# new_sawtag_2012.net
KiCad netlist of a schematic drawn in EAGLE
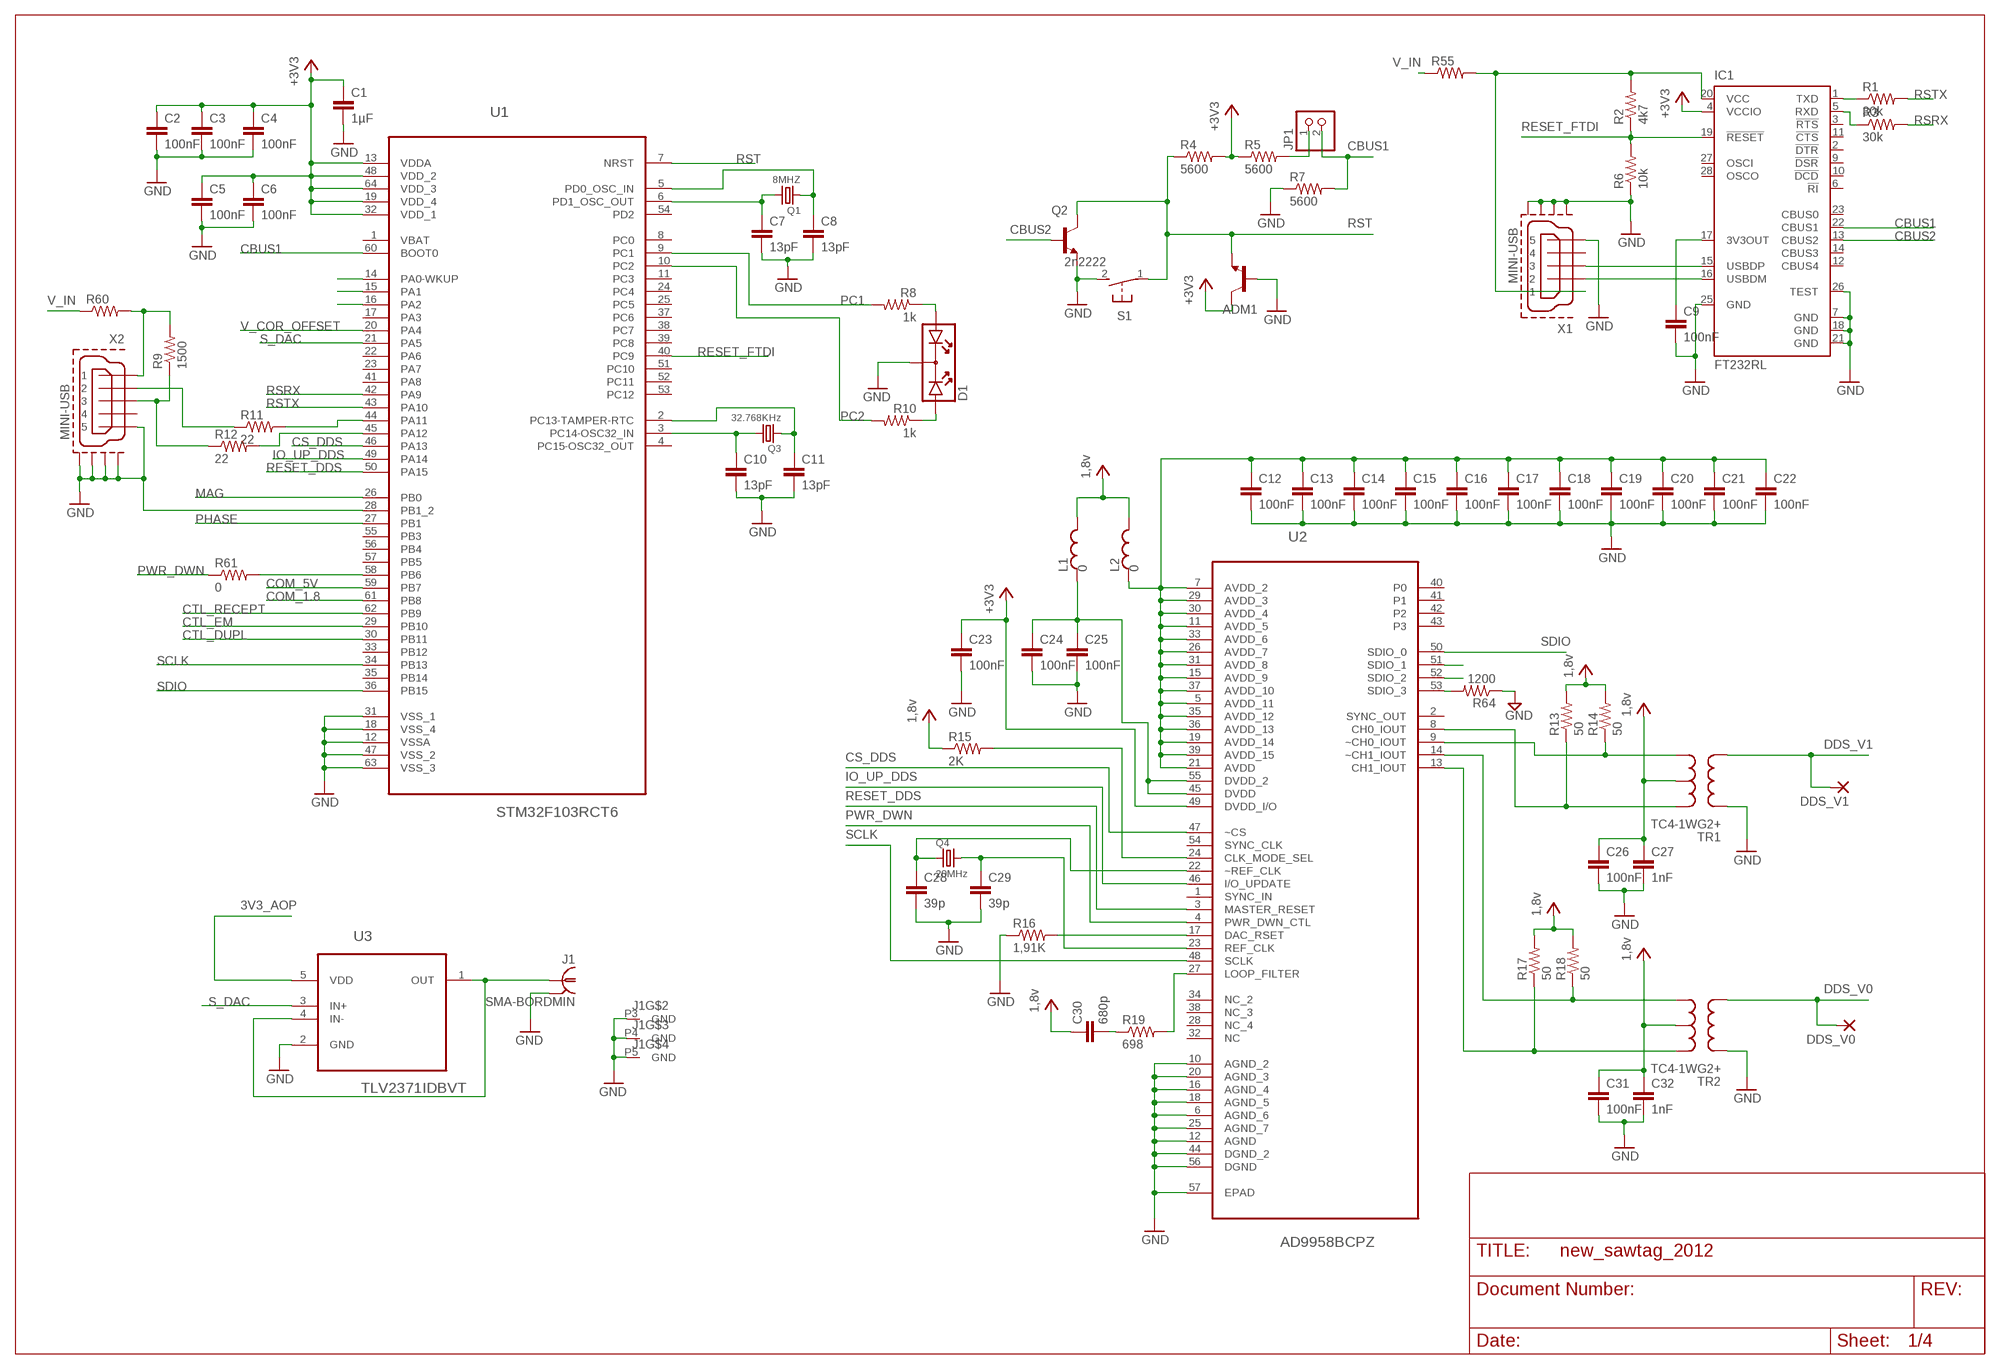
[diagram p0: schematic, sheet 1]
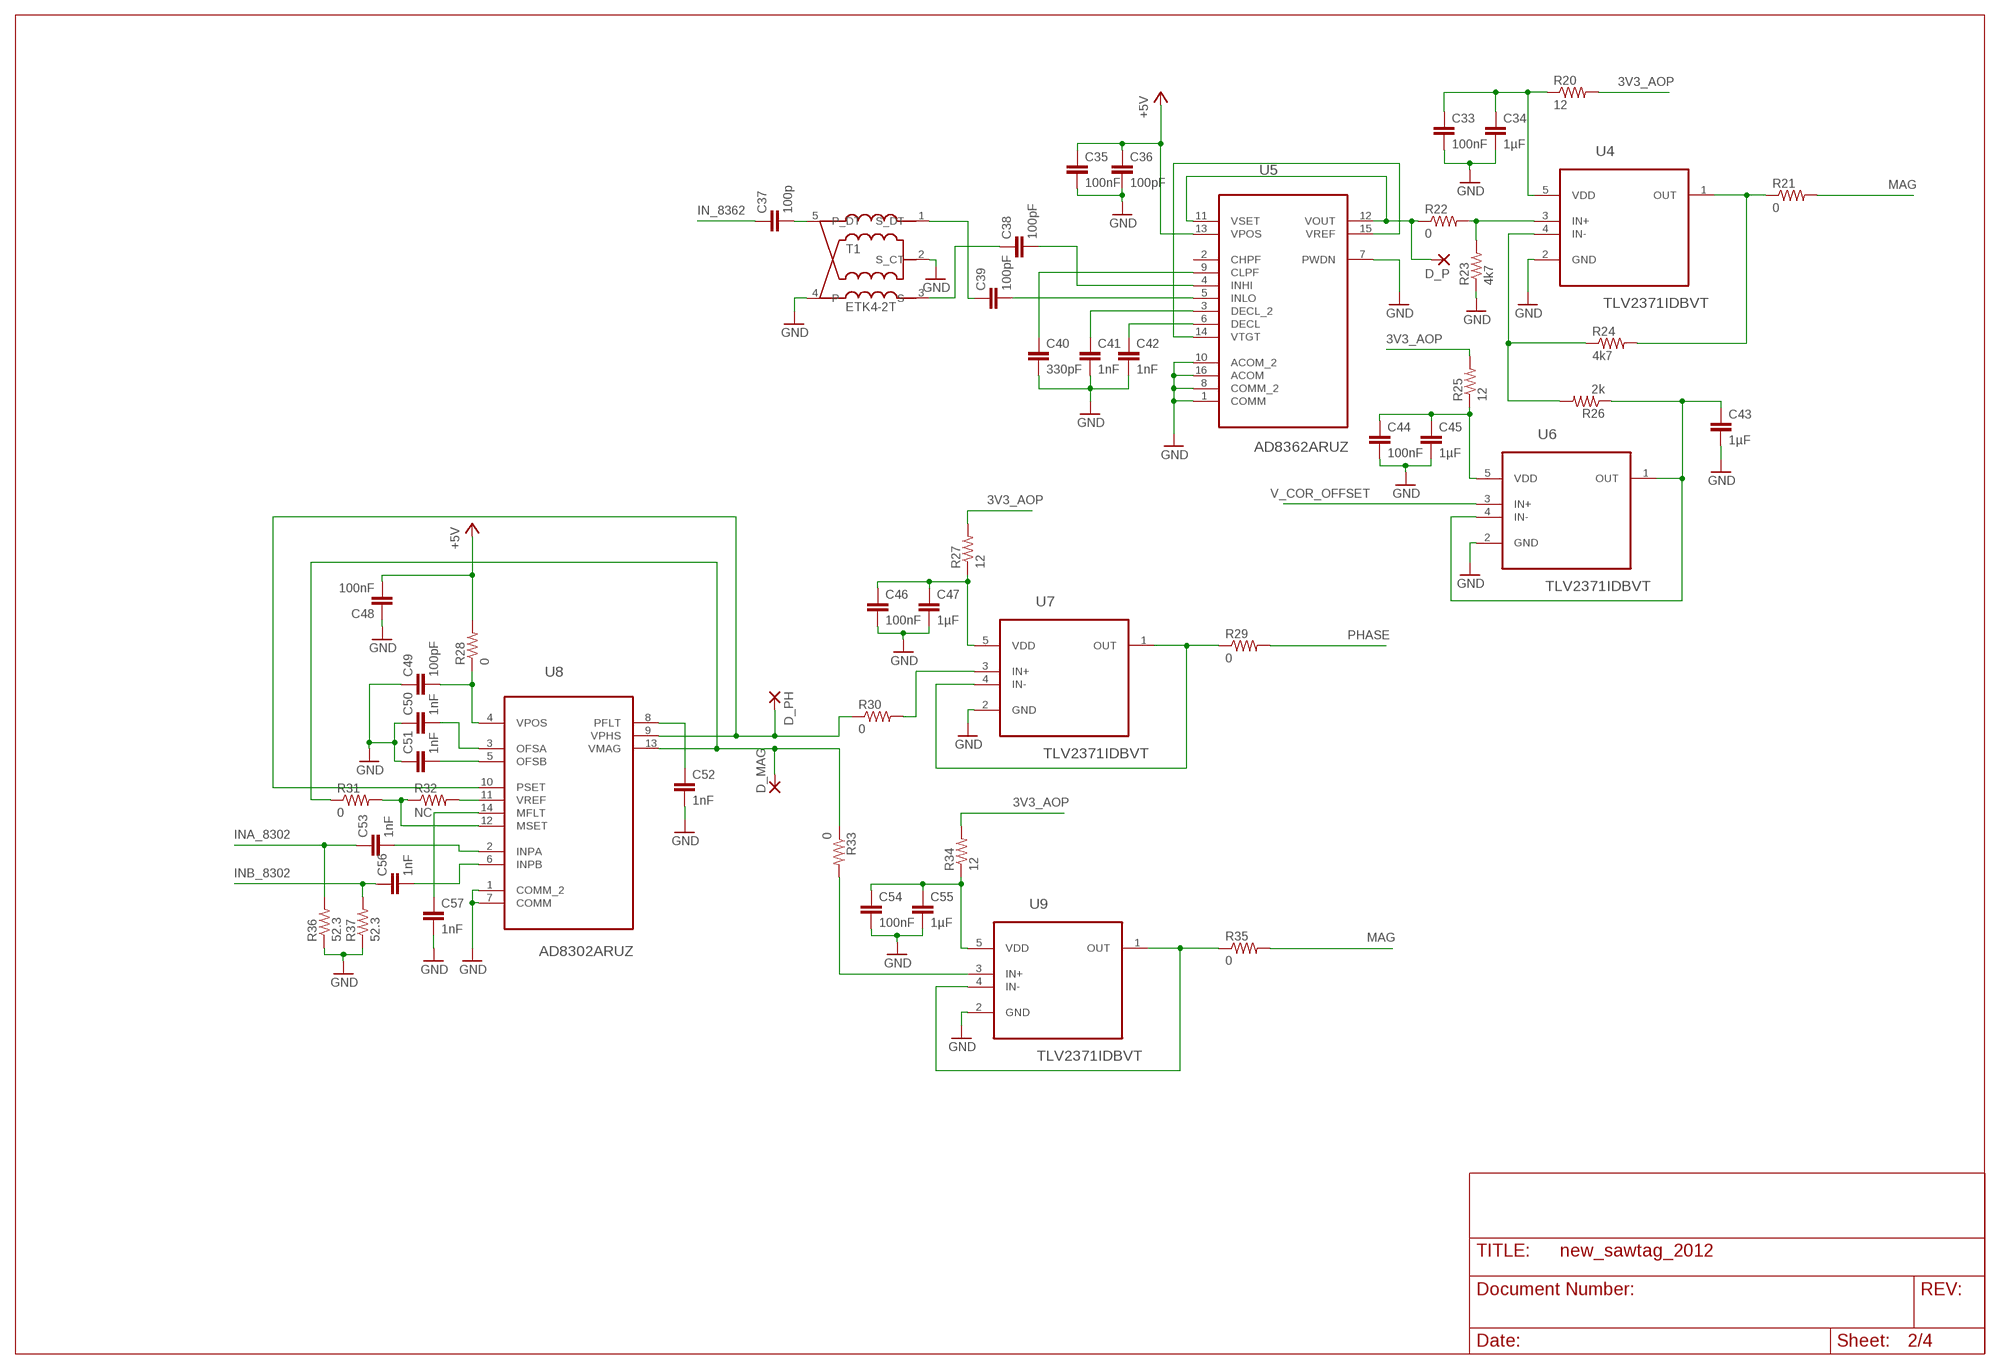
[diagram p1: schematic, sheet 2]
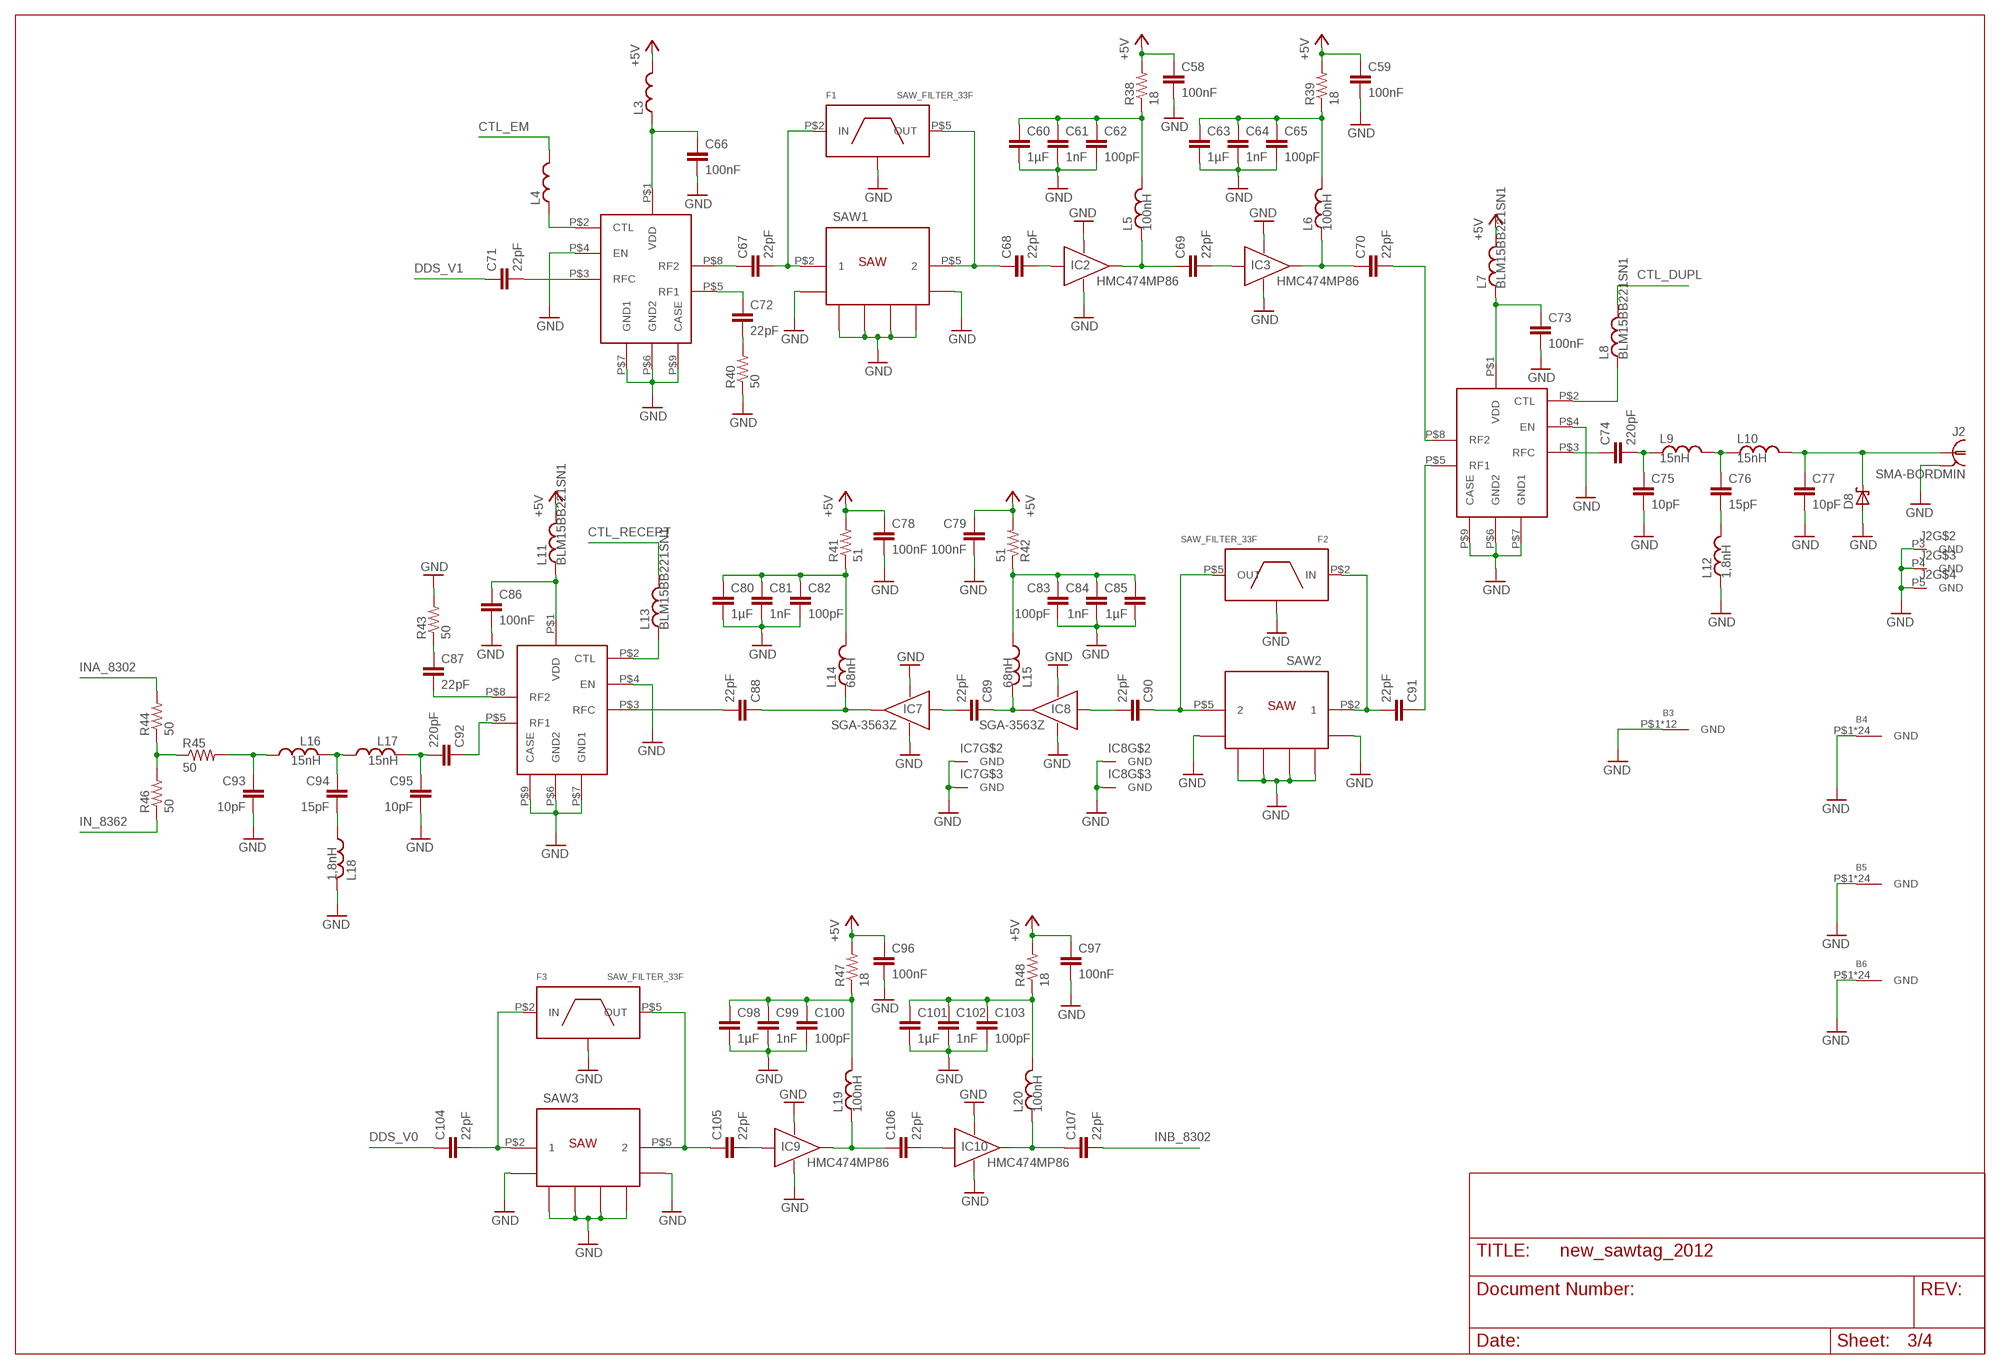
[diagram p2: schematic, sheet 3]
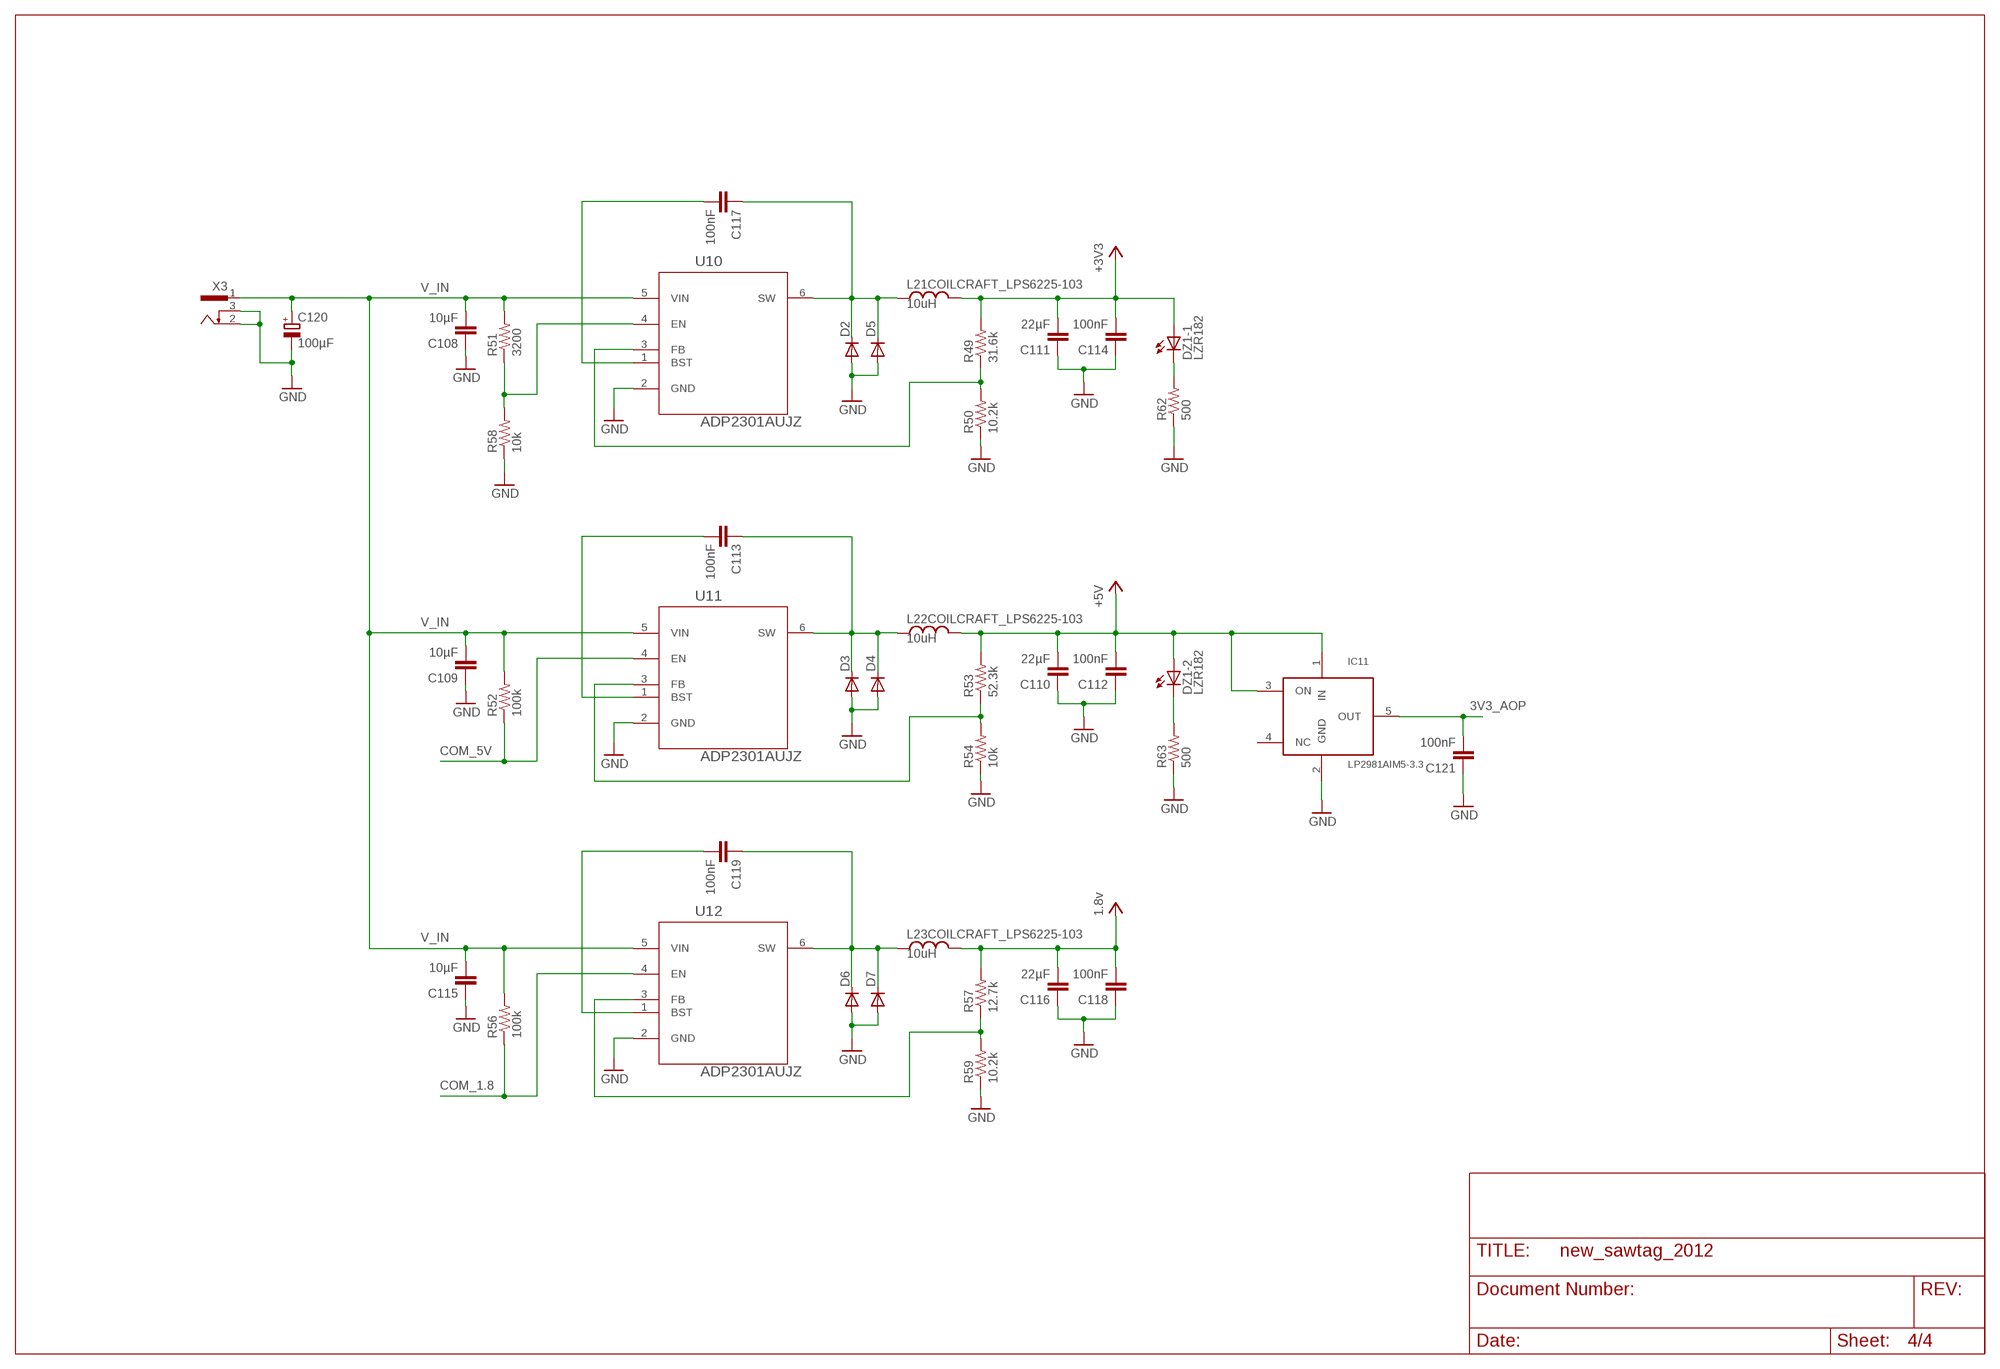
[diagram p3: schematic, sheet 4]

(export (version "E")
  (design (tool "Eeschema 10.0.6"))
  (components
    (comp (ref "ADM1")
      (value "TRANSISTOR_NPNSOT23")
      (footprint "eagle-import:SOT23")
      (libsource (lib "eagle-import") (part "TRANSISTOR_NPNSOT23"))
    )
    (comp (ref "C1")
      (value "1µF")
      (footprint "eagle-import:C0805")
      (libsource (lib "eagle-import") (part "C-EUC0805"))
    )
    (comp (ref "C2")
      (value "100nF")
      (footprint "eagle-import:C0603")
      (libsource (lib "eagle-import") (part "C-EUC0603"))
    )
    (comp (ref "C3")
      (value "100nF")
      (footprint "eagle-import:C0603")
      (libsource (lib "eagle-import") (part "C-EUC0603"))
    )
    (comp (ref "C4")
      (value "100nF")
      (footprint "eagle-import:C0603")
      (libsource (lib "eagle-import") (part "C-EUC0603"))
    )
    (comp (ref "C5")
      (value "100nF")
      (footprint "eagle-import:C0603")
      (libsource (lib "eagle-import") (part "C-EUC0603"))
    )
    (comp (ref "C6")
      (value "100nF")
      (footprint "eagle-import:C0603")
      (libsource (lib "eagle-import") (part "C-EUC0603"))
    )
    (comp (ref "C7")
      (value "13pF")
      (footprint "eagle-import:C0603")
      (libsource (lib "eagle-import") (part "C-EUC0603"))
    )
    (comp (ref "C8")
      (value "13pF")
      (footprint "eagle-import:C0603")
      (libsource (lib "eagle-import") (part "C-EUC0603"))
    )
    (comp (ref "C9")
      (value "100nF")
      (footprint "eagle-import:C0603")
      (libsource (lib "eagle-import") (part "C-EUC0603"))
    )
    (comp (ref "C10")
      (value "13pF")
      (footprint "eagle-import:C0603")
      (libsource (lib "eagle-import") (part "C-EUC0603"))
    )
    (comp (ref "C11")
      (value "13pF")
      (footprint "eagle-import:C0603")
      (libsource (lib "eagle-import") (part "C-EUC0603"))
    )
    (comp (ref "C12")
      (value "100nF")
      (footprint "eagle-import:C0402")
      (libsource (lib "eagle-import") (part "C-EUC0402"))
    )
    (comp (ref "C13")
      (value "100nF")
      (footprint "eagle-import:C0402")
      (libsource (lib "eagle-import") (part "C-EUC0402"))
    )
    (comp (ref "C14")
      (value "100nF")
      (footprint "eagle-import:C0402")
      (libsource (lib "eagle-import") (part "C-EUC0402"))
    )
    (comp (ref "C15")
      (value "100nF")
      (footprint "eagle-import:C0402")
      (libsource (lib "eagle-import") (part "C-EUC0402"))
    )
    (comp (ref "C16")
      (value "100nF")
      (footprint "eagle-import:C0402")
      (libsource (lib "eagle-import") (part "C-EUC0402"))
    )
    (comp (ref "C17")
      (value "100nF")
      (footprint "eagle-import:C0402")
      (libsource (lib "eagle-import") (part "C-EUC0402"))
    )
    (comp (ref "C18")
      (value "100nF")
      (footprint "eagle-import:C0402")
      (libsource (lib "eagle-import") (part "C-EUC0402"))
    )
    (comp (ref "C19")
      (value "100nF")
      (footprint "eagle-import:C0402")
      (libsource (lib "eagle-import") (part "C-EUC0402"))
    )
    (comp (ref "C20")
      (value "100nF")
      (footprint "eagle-import:C0402")
      (libsource (lib "eagle-import") (part "C-EUC0402"))
    )
    (comp (ref "C21")
      (value "100nF")
      (footprint "eagle-import:C0402")
      (libsource (lib "eagle-import") (part "C-EUC0402"))
    )
    (comp (ref "C22")
      (value "100nF")
      (footprint "eagle-import:C0402")
      (libsource (lib "eagle-import") (part "C-EUC0402"))
    )
    (comp (ref "C23")
      (value "100nF")
      (footprint "eagle-import:C0603")
      (libsource (lib "eagle-import") (part "C-EUC0603"))
    )
    (comp (ref "C24")
      (value "100nF")
      (footprint "eagle-import:C0603")
      (libsource (lib "eagle-import") (part "C-EUC0603"))
    )
    (comp (ref "C25")
      (value "100nF")
      (footprint "eagle-import:C0603")
      (libsource (lib "eagle-import") (part "C-EUC0603"))
    )
    (comp (ref "C26")
      (value "100nF")
      (footprint "eagle-import:C0603")
      (libsource (lib "eagle-import") (part "C-EUC0603"))
    )
    (comp (ref "C27")
      (value "1nF")
      (footprint "eagle-import:C0402")
      (libsource (lib "eagle-import") (part "C-EUC0402"))
    )
    (comp (ref "C28")
      (value "39p")
      (footprint "eagle-import:C0402")
      (libsource (lib "eagle-import") (part "C-EUC0402"))
    )
    (comp (ref "C29")
      (value "39p")
      (footprint "eagle-import:C0402")
      (libsource (lib "eagle-import") (part "C-EUC0402"))
    )
    (comp (ref "C30")
      (value "680p")
      (footprint "eagle-import:C0402")
      (libsource (lib "eagle-import") (part "C-EUC0402"))
    )
    (comp (ref "C31")
      (value "100nF")
      (footprint "eagle-import:C0603")
      (libsource (lib "eagle-import") (part "C-EUC0603"))
    )
    (comp (ref "C32")
      (value "1nF")
      (footprint "eagle-import:C0402")
      (libsource (lib "eagle-import") (part "C-EUC0402"))
    )
    (comp (ref "D1")
      (value "DUOLED")
      (footprint "eagle-import:DUOLED")
      (libsource (lib "eagle-import") (part "DUOLED"))
    )
    (comp (ref "DDS_V0")
      (value "1,6/0,8")
      (footprint "eagle-import:1,6_0,8")
      (libsource (lib "eagle-import") (part "1,6/0,8"))
    )
    (comp (ref "DDS_V1")
      (value "1,6/0,8")
      (footprint "eagle-import:1,6_0,8")
      (libsource (lib "eagle-import") (part "1,6/0,8"))
    )
    (comp (ref "IC1")
      (value "FT232RL")
      (footprint "eagle-import:SSOP28")
      (libsource (lib "eagle-import") (part "FT232RL"))
    )
    (comp (ref "J1")
      (value "SMA-BORDMIN")
      (footprint "eagle-import:SMA_BORDMIN")
      (libsource (lib "eagle-import") (part "SMA-BORDMIN"))
    )
    (comp (ref "JP1")
      (value "PINHD-1X2")
      (footprint "eagle-import:1X02")
      (libsource (lib "eagle-import") (part "PINHD-1X2"))
    )
    (comp (ref "L1")
      (value "0")
      (footprint "eagle-import:0603")
      (libsource (lib "eagle-import") (part "L_0603"))
    )
    (comp (ref "L2")
      (value "0")
      (footprint "eagle-import:0603")
      (libsource (lib "eagle-import") (part "L_0603"))
    )
    (comp (ref "Q1")
      (value "8MHZ")
      (footprint "eagle-import:SMD_5_3")
      (libsource (lib "eagle-import") (part "Q_20MHZ_SMD"))
    )
    (comp (ref "Q2")
      (value "2n2222")
      (footprint "eagle-import:SOT23")
      (libsource (lib "eagle-import") (part "TRANSISTOR_NPNSOT23"))
    )
    (comp (ref "Q3")
      (value "32.768KHz")
      (footprint "eagle-import:SMD_32K")
      (libsource (lib "eagle-import") (part "Q_32K_SMD"))
    )
    (comp (ref "Q4")
      (value "20MHz")
      (footprint "eagle-import:SMD_5_3")
      (libsource (lib "eagle-import") (part "Q_20MHZ_SMD"))
    )
    (comp (ref "R1")
      (value "30k")
      (footprint "eagle-import:R0402")
      (libsource (lib "eagle-import") (part "R-US_R0402"))
    )
    (comp (ref "R2")
      (value "4k7")
      (footprint "eagle-import:R0402")
      (libsource (lib "eagle-import") (part "R-US_R0402"))
    )
    (comp (ref "R3")
      (value "30k")
      (footprint "eagle-import:R0402")
      (libsource (lib "eagle-import") (part "R-US_R0402"))
    )
    (comp (ref "R4")
      (value "5600")
      (footprint "eagle-import:R0603")
      (libsource (lib "eagle-import") (part "R-US_R0603"))
    )
    (comp (ref "R5")
      (value "5600")
      (footprint "eagle-import:R0603")
      (libsource (lib "eagle-import") (part "R-US_R0603"))
    )
    (comp (ref "R6")
      (value "10k")
      (footprint "eagle-import:R0402")
      (libsource (lib "eagle-import") (part "R-US_R0402"))
    )
    (comp (ref "R7")
      (value "5600")
      (footprint "eagle-import:R0603")
      (libsource (lib "eagle-import") (part "R-US_R0603"))
    )
    (comp (ref "R8")
      (value "1k")
      (footprint "eagle-import:R0603")
      (libsource (lib "eagle-import") (part "R-US_R0603"))
    )
    (comp (ref "R9")
      (value "1500")
      (footprint "eagle-import:R1206")
      (libsource (lib "eagle-import") (part "R-US_R1206"))
    )
    (comp (ref "R10")
      (value "1k")
      (footprint "eagle-import:R0603")
      (libsource (lib "eagle-import") (part "R-US_R0603"))
    )
    (comp (ref "R11")
      (value "22")
      (footprint "eagle-import:R0603")
      (libsource (lib "eagle-import") (part "R-US_R0603"))
    )
    (comp (ref "R12")
      (value "22")
      (footprint "eagle-import:R0603")
      (libsource (lib "eagle-import") (part "R-US_R0603"))
    )
    (comp (ref "R13")
      (value "50")
      (footprint "eagle-import:R0402")
      (libsource (lib "eagle-import") (part "R-US_R0402"))
    )
    (comp (ref "R14")
      (value "50")
      (footprint "eagle-import:R0402")
      (libsource (lib "eagle-import") (part "R-US_R0402"))
    )
    (comp (ref "R15")
      (value "2K")
      (footprint "eagle-import:R0402")
      (libsource (lib "eagle-import") (part "R-US_R0402"))
    )
    (comp (ref "R16")
      (value "1,91K")
      (footprint "eagle-import:R0402")
      (libsource (lib "eagle-import") (part "R-US_R0402"))
    )
    (comp (ref "R17")
      (value "50")
      (footprint "eagle-import:R0402")
      (libsource (lib "eagle-import") (part "R-US_R0402"))
    )
    (comp (ref "R18")
      (value "50")
      (footprint "eagle-import:R0402")
      (libsource (lib "eagle-import") (part "R-US_R0402"))
    )
    (comp (ref "R19")
      (value "698")
      (footprint "eagle-import:R0402")
      (libsource (lib "eagle-import") (part "R-US_R0402"))
    )
    (comp (ref "R55")
      (value "R-US_R2512")
      (footprint "eagle-import:R2512")
      (libsource (lib "eagle-import") (part "R-US_R2512"))
    )
    (comp (ref "R60")
      (value "R-US_R2512")
      (footprint "eagle-import:R2512")
      (libsource (lib "eagle-import") (part "R-US_R2512"))
    )
    (comp (ref "R61")
      (value "0")
      (footprint "eagle-import:R0603")
      (libsource (lib "eagle-import") (part "R-US_R0603"))
    )
    (comp (ref "R64")
      (value "1200")
      (footprint "eagle-import:R0402")
      (libsource (lib "eagle-import") (part "R-US_R0402"))
    )
    (comp (ref "S1")
      (value "31-XX")
      (footprint "eagle-import:B3F-31XX")
      (fields (field (name "MPN") "B3F-3100"))
      (libsource (lib "eagle-import") (part "31-XX"))
    )
    (comp (ref "TR1")
      (value "TC4-1WG2+")
      (footprint "eagle-import:AT224-3")
      (libsource (lib "eagle-import") (part "TC4-1WG2+"))
    )
    (comp (ref "TR2")
      (value "TC4-1WG2+")
      (footprint "eagle-import:AT224-3")
      (libsource (lib "eagle-import") (part "TC4-1WG2+"))
    )
    (comp (ref "U1")
      (value "STM32F103RCT6")
      (footprint "eagle-import:QFP50P1200X1200X160-64N")
      (libsource (lib "eagle-import") (part "STM32F103RCT6"))
    )
    (comp (ref "U2")
      (value "AD9958BCPZ")
      (footprint "eagle-import:QFN50P800X800X100-57N")
      (libsource (lib "eagle-import") (part "AD9958BCPZ"))
    )
    (comp (ref "U3")
      (value "TLV2371IDBVT")
      (footprint "eagle-import:SOT95P280X145-5N")
      (libsource (lib "eagle-import") (part "TLV2371IDBVT"))
    )
    (comp (ref "X1")
      (value "MINI-USB")
      (footprint "eagle-import:UX60-MB-5ST")
      (libsource (lib "eagle-import") (part "MINI-USB-SHIELD-UX60-MB-5ST"))
    )
    (comp (ref "X2")
      (value "MINI-USB")
      (footprint "eagle-import:UX60-MB-5ST")
      (libsource (lib "eagle-import") (part "MINI-USB-SHIELD-UX60-MB-5ST"))
    )
    (comp (ref "C108")
      (value "10µF")
      (footprint "eagle-import:C0805")
      (libsource (lib "eagle-import") (part "C-EUC0805"))
    )
    (comp (ref "C109")
      (value "10µF")
      (footprint "eagle-import:C0805")
      (libsource (lib "eagle-import") (part "C-EUC0805"))
    )
    (comp (ref "C110")
      (value "22µF")
      (footprint "eagle-import:C0805")
      (libsource (lib "eagle-import") (part "C-EUC0805"))
    )
    (comp (ref "C111")
      (value "22µF")
      (footprint "eagle-import:C0805")
      (libsource (lib "eagle-import") (part "C-EUC0805"))
    )
    (comp (ref "C112")
      (value "100nF")
      (footprint "eagle-import:C0805")
      (libsource (lib "eagle-import") (part "C-EUC0805"))
    )
    (comp (ref "C113")
      (value "100nF")
      (footprint "eagle-import:C0805")
      (libsource (lib "eagle-import") (part "C-EUC0805"))
    )
    (comp (ref "C114")
      (value "100nF")
      (footprint "eagle-import:C0805")
      (libsource (lib "eagle-import") (part "C-EUC0805"))
    )
    (comp (ref "C115")
      (value "10µF")
      (footprint "eagle-import:C0805")
      (libsource (lib "eagle-import") (part "C-EUC0805"))
    )
    (comp (ref "C116")
      (value "22µF")
      (footprint "eagle-import:C0805")
      (libsource (lib "eagle-import") (part "C-EUC0805"))
    )
    (comp (ref "C117")
      (value "100nF")
      (footprint "eagle-import:C0805")
      (libsource (lib "eagle-import") (part "C-EUC0805"))
    )
    (comp (ref "C118")
      (value "100nF")
      (footprint "eagle-import:C0805")
      (libsource (lib "eagle-import") (part "C-EUC0805"))
    )
    (comp (ref "C119")
      (value "100nF")
      (footprint "eagle-import:C0603")
      (libsource (lib "eagle-import") (part "C-EUC0603"))
    )
    (comp (ref "C120")
      (value "100µF")
      (footprint "eagle-import:140CLH-1010")
      (libsource (lib "eagle-import") (part "CPOL-EU140CLH-1010"))
    )
    (comp (ref "C121")
      (value "100nF")
      (footprint "eagle-import:C0805")
      (libsource (lib "eagle-import") (part "C-EUC0805"))
    )
    (comp (ref "D2")
      (value "DIODE-SMB")
      (footprint "eagle-import:SMB")
      (libsource (lib "eagle-import") (part "DIODE-SMB"))
    )
    (comp (ref "D3")
      (value "DIODE-SMB")
      (footprint "eagle-import:SMB")
      (libsource (lib "eagle-import") (part "DIODE-SMB"))
    )
    (comp (ref "D4")
      (value "DIODE-SMC")
      (footprint "eagle-import:SMC")
      (libsource (lib "eagle-import") (part "DIODE-SMC"))
    )
    (comp (ref "D5")
      (value "DIODE-SMC")
      (footprint "eagle-import:SMC")
      (libsource (lib "eagle-import") (part "DIODE-SMC"))
    )
    (comp (ref "D6")
      (value "DIODE-SMB")
      (footprint "eagle-import:SMB")
      (libsource (lib "eagle-import") (part "DIODE-SMB"))
    )
    (comp (ref "D7")
      (value "DIODE-SMC")
      (footprint "eagle-import:SMC")
      (libsource (lib "eagle-import") (part "DIODE-SMC"))
    )
    (comp (ref "DZ1")
      (value "LZR182")
      (footprint "eagle-import:LZR182")
      (libsource (lib "eagle-import") (part "LZR182"))
    )
    (comp (ref "IC11")
      (value "LP2981AIM5-3.3")
      (footprint "eagle-import:SOT23-M5")
      (libsource (lib "eagle-import") (part "LP2981AIM5-3.3"))
    )
    (comp (ref "L21COILCRAFT_LPS6225-103")
      (value "10uH")
      (footprint "eagle-import:L_DCDC_6_6")
      (libsource (lib "eagle-import") (part "LPS6225"))
    )
    (comp (ref "L22COILCRAFT_LPS6225-103")
      (value "10uH")
      (footprint "eagle-import:L_DCDC_6_6")
      (libsource (lib "eagle-import") (part "LPS6225"))
    )
    (comp (ref "L23COILCRAFT_LPS6225-103")
      (value "10uH")
      (footprint "eagle-import:L_DCDC_6_6")
      (libsource (lib "eagle-import") (part "LPS6225"))
    )
    (comp (ref "R49")
      (value "31.6k")
      (footprint "eagle-import:R0603")
      (libsource (lib "eagle-import") (part "R-US_R0603"))
    )
    (comp (ref "R50")
      (value "10.2k")
      (footprint "eagle-import:R0603")
      (libsource (lib "eagle-import") (part "R-US_R0603"))
    )
    (comp (ref "R51")
      (value "3200")
      (footprint "eagle-import:R0603")
      (libsource (lib "eagle-import") (part "R-US_R0603"))
    )
    (comp (ref "R52")
      (value "100k")
      (footprint "eagle-import:R0603")
      (libsource (lib "eagle-import") (part "R-US_R0603"))
    )
    (comp (ref "R53")
      (value "52.3k")
      (footprint "eagle-import:R0603")
      (libsource (lib "eagle-import") (part "R-US_R0603"))
    )
    (comp (ref "R54")
      (value "10k")
      (footprint "eagle-import:R0603")
      (libsource (lib "eagle-import") (part "R-US_R0603"))
    )
    (comp (ref "R56")
      (value "100k")
      (footprint "eagle-import:R0603")
      (libsource (lib "eagle-import") (part "R-US_R0603"))
    )
    (comp (ref "R57")
      (value "12.7k")
      (footprint "eagle-import:R0603")
      (libsource (lib "eagle-import") (part "R-US_R0603"))
    )
    (comp (ref "R58")
      (value "10k")
      (footprint "eagle-import:R0603")
      (libsource (lib "eagle-import") (part "R-US_R0603"))
    )
    (comp (ref "R59")
      (value "10.2k")
      (footprint "eagle-import:R0603")
      (libsource (lib "eagle-import") (part "R-US_R0603"))
    )
    (comp (ref "R62")
      (value "500")
      (footprint "eagle-import:R0402")
      (libsource (lib "eagle-import") (part "R-US_R0402"))
    )
    (comp (ref "R63")
      (value "500")
      (footprint "eagle-import:R0402")
      (libsource (lib "eagle-import") (part "R-US_R0402"))
    )
    (comp (ref "U10")
      (value "ADP2301AUJZ")
      (footprint "eagle-import:SOT95P280X90-6N")
      (libsource (lib "eagle-import") (part "ADP2301AUJZ"))
    )
    (comp (ref "U11")
      (value "ADP2301AUJZ")
      (footprint "eagle-import:SOT95P280X90-6N")
      (libsource (lib "eagle-import") (part "ADP2301AUJZ"))
    )
    (comp (ref "U12")
      (value "ADP2301AUJZ")
      (footprint "eagle-import:SOT95P280X90-6N")
      (libsource (lib "eagle-import") (part "ADP2301AUJZ"))
    )
    (comp (ref "X3")
      (value "733980-62")
      (footprint "eagle-import:733980-62")
      (libsource (lib "eagle-import") (part "73398?0-62"))
    )
    (comp (ref "C33")
      (value "100nF")
      (footprint "eagle-import:C0402")
      (libsource (lib "eagle-import") (part "C-EUC0402"))
    )
    (comp (ref "C34")
      (value "1µF")
      (footprint "eagle-import:C0603")
      (libsource (lib "eagle-import") (part "C-EUC0603"))
    )
    (comp (ref "C35")
      (value "100nF")
      (footprint "eagle-import:C0603")
      (libsource (lib "eagle-import") (part "C-EUC0603"))
    )
    (comp (ref "C36")
      (value "100pF")
      (footprint "eagle-import:C0603")
      (libsource (lib "eagle-import") (part "C-EUC0603"))
    )
    (comp (ref "C37")
      (value "100p")
      (footprint "eagle-import:C0402")
      (libsource (lib "eagle-import") (part "C-EUC0402"))
    )
    (comp (ref "C38")
      (value "100pF")
      (footprint "eagle-import:C0402")
      (libsource (lib "eagle-import") (part "C-EUC0402"))
    )
    (comp (ref "C39")
      (value "100pF")
      (footprint "eagle-import:C0402")
      (libsource (lib "eagle-import") (part "C-EUC0402"))
    )
    (comp (ref "C40")
      (value "330pF")
      (footprint "eagle-import:C0603")
      (libsource (lib "eagle-import") (part "C-EUC0603"))
    )
    (comp (ref "C41")
      (value "1nF")
      (footprint "eagle-import:C0603")
      (libsource (lib "eagle-import") (part "C-EUC0603"))
    )
    (comp (ref "C42")
      (value "1nF")
      (footprint "eagle-import:C0603")
      (libsource (lib "eagle-import") (part "C-EUC0603"))
    )
    (comp (ref "C43")
      (value "1µF")
      (footprint "eagle-import:C0603")
      (libsource (lib "eagle-import") (part "C-EUC0603"))
    )
    (comp (ref "C44")
      (value "100nF")
      (footprint "eagle-import:C0402")
      (libsource (lib "eagle-import") (part "C-EUC0402"))
    )
    (comp (ref "C45")
      (value "1µF")
      (footprint "eagle-import:C0603")
      (libsource (lib "eagle-import") (part "C-EUC0603"))
    )
    (comp (ref "C46")
      (value "100nF")
      (footprint "eagle-import:C0402")
      (libsource (lib "eagle-import") (part "C-EUC0402"))
    )
    (comp (ref "C47")
      (value "1µF")
      (footprint "eagle-import:C0603")
      (libsource (lib "eagle-import") (part "C-EUC0603"))
    )
    (comp (ref "C48")
      (value "100nF")
      (footprint "eagle-import:C0603")
      (libsource (lib "eagle-import") (part "C-EUC0603"))
    )
    (comp (ref "C49")
      (value "100pF")
      (footprint "eagle-import:C0402")
      (libsource (lib "eagle-import") (part "C-EUC0402"))
    )
    (comp (ref "C50")
      (value "1nF")
      (footprint "eagle-import:C0402")
      (libsource (lib "eagle-import") (part "C-EUC0402"))
    )
    (comp (ref "C51")
      (value "1nF")
      (footprint "eagle-import:C0402")
      (libsource (lib "eagle-import") (part "C-EUC0402"))
    )
    (comp (ref "C52")
      (value "1nF")
      (footprint "eagle-import:C0402")
      (libsource (lib "eagle-import") (part "C-EUC0402"))
    )
    (comp (ref "C53")
      (value "1nF")
      (footprint "eagle-import:C0402")
      (libsource (lib "eagle-import") (part "C-EUC0402"))
    )
    (comp (ref "C54")
      (value "100nF")
      (footprint "eagle-import:C0402")
      (libsource (lib "eagle-import") (part "C-EUC0402"))
    )
    (comp (ref "C55")
      (value "1µF")
      (footprint "eagle-import:C0603")
      (libsource (lib "eagle-import") (part "C-EUC0603"))
    )
    (comp (ref "C56")
      (value "1nF")
      (footprint "eagle-import:C0402")
      (libsource (lib "eagle-import") (part "C-EUC0402"))
    )
    (comp (ref "C57")
      (value "1nF")
      (footprint "eagle-import:C0402")
      (libsource (lib "eagle-import") (part "C-EUC0402"))
    )
    (comp (ref "D_MAG")
      (value "1,6/0,8")
      (footprint "eagle-import:1,6_0,8")
      (libsource (lib "eagle-import") (part "1,6/0,8"))
    )
    (comp (ref "D_P")
      (value "1,6/0,8")
      (footprint "eagle-import:1,6_0,8")
      (libsource (lib "eagle-import") (part "1,6/0,8"))
    )
    (comp (ref "D_PH")
      (value "1,6/0,8")
      (footprint "eagle-import:1,6_0,8")
      (libsource (lib "eagle-import") (part "1,6/0,8"))
    )
    (comp (ref "R20")
      (value "12")
      (footprint "eagle-import:R0603")
      (libsource (lib "eagle-import") (part "R-US_R0603"))
    )
    (comp (ref "R21")
      (value "0")
      (footprint "eagle-import:R0603")
      (libsource (lib "eagle-import") (part "R-US_R0603"))
    )
    (comp (ref "R22")
      (value "0")
      (footprint "eagle-import:R0603")
      (libsource (lib "eagle-import") (part "R-US_R0603"))
    )
    (comp (ref "R23")
      (value "4k7")
      (footprint "eagle-import:R0603")
      (libsource (lib "eagle-import") (part "R-US_R0603"))
    )
    (comp (ref "R24")
      (value "4k7")
      (footprint "eagle-import:R0603")
      (libsource (lib "eagle-import") (part "R-US_R0603"))
    )
    (comp (ref "R25")
      (value "12")
      (footprint "eagle-import:R0603")
      (libsource (lib "eagle-import") (part "R-US_R0603"))
    )
    (comp (ref "R26")
      (value "2k")
      (footprint "eagle-import:R0603")
      (libsource (lib "eagle-import") (part "R-US_R0603"))
    )
    (comp (ref "R27")
      (value "12")
      (footprint "eagle-import:R0603")
      (libsource (lib "eagle-import") (part "R-US_R0603"))
    )
    (comp (ref "R28")
      (value "0")
      (footprint "eagle-import:R0603")
      (libsource (lib "eagle-import") (part "R-US_R0603"))
    )
    (comp (ref "R29")
      (value "0")
      (footprint "eagle-import:R0603")
      (libsource (lib "eagle-import") (part "R-US_R0603"))
    )
    (comp (ref "R30")
      (value "0")
      (footprint "eagle-import:R0603")
      (libsource (lib "eagle-import") (part "R-US_R0603"))
    )
    (comp (ref "R31")
      (value "0")
      (footprint "eagle-import:R0603")
      (libsource (lib "eagle-import") (part "R-US_R0603"))
    )
    (comp (ref "R32")
      (value "NC")
      (footprint "eagle-import:R0603")
      (libsource (lib "eagle-import") (part "R-US_R0603"))
    )
    (comp (ref "R33")
      (value "0")
      (footprint "eagle-import:R0603")
      (libsource (lib "eagle-import") (part "R-US_R0603"))
    )
    (comp (ref "R34")
      (value "12")
      (footprint "eagle-import:R0603")
      (libsource (lib "eagle-import") (part "R-US_R0603"))
    )
    (comp (ref "R35")
      (value "0")
      (footprint "eagle-import:R0603")
      (libsource (lib "eagle-import") (part "R-US_R0603"))
    )
    (comp (ref "R36")
      (value "52.3")
      (footprint "eagle-import:R0603")
      (libsource (lib "eagle-import") (part "R-US_R0603"))
    )
    (comp (ref "R37")
      (value "52.3")
      (footprint "eagle-import:R0603")
      (libsource (lib "eagle-import") (part "R-US_R0603"))
    )
    (comp (ref "T1")
      (value "ETK4-2T")
      (footprint "eagle-import:SM-22")
      (libsource (lib "eagle-import") (part "ETK4-2T"))
    )
    (comp (ref "U4")
      (value "TLV2371IDBVT")
      (footprint "eagle-import:SOT95P280X145-5N")
      (libsource (lib "eagle-import") (part "TLV2371IDBVT"))
    )
    (comp (ref "U5")
      (value "AD8362ARUZ")
      (footprint "eagle-import:SOP65P640X120-16N")
      (libsource (lib "eagle-import") (part "AD8362ARUZ"))
    )
    (comp (ref "U6")
      (value "TLV2371IDBVT")
      (footprint "eagle-import:SOT95P280X145-5N")
      (fields
        (field (name "MPN") "TLV2371IDBVT")
        (field (name "OC_FARNELL") "8454990")
        (field (name "OC_NEWARK") "76C7970")
        (field (name "PACKAGE") "SOT-23-5")
        (field (name "SUPPLIER") "Texas Instruments")
      )
      (libsource (lib "eagle-import") (part "TLV2371IDBVT"))
    )
    (comp (ref "U7")
      (value "TLV2371IDBVT")
      (footprint "eagle-import:SOT95P280X145-5N")
      (fields
        (field (name "MPN") "TLV2371IDBVT")
        (field (name "OC_FARNELL") "8454990")
        (field (name "OC_NEWARK") "76C7970")
        (field (name "PACKAGE") "SOT-23-5")
        (field (name "SUPPLIER") "Texas Instruments")
      )
      (libsource (lib "eagle-import") (part "TLV2371IDBVT"))
    )
    (comp (ref "U8")
      (value "AD8302ARUZ")
      (footprint "eagle-import:SOP65P640X120-14N")
      (libsource (lib "eagle-import") (part "AD8302ARUZ"))
    )
    (comp (ref "U9")
      (value "TLV2371IDBVT")
      (footprint "eagle-import:SOT95P280X145-5N")
      (fields
        (field (name "MPN") "TLV2371IDBVT")
        (field (name "OC_FARNELL") "8454990")
        (field (name "OC_NEWARK") "76C7970")
        (field (name "PACKAGE") "SOT-23-5")
        (field (name "SUPPLIER") "Texas Instruments")
      )
      (libsource (lib "eagle-import") (part "TLV2371IDBVT"))
    )
    (comp (ref "B3")
      (value "BMIS-102")
      (footprint "eagle-import:BMIS-102")
      (libsource (lib "eagle-import") (part "BMIS-102"))
    )
    (comp (ref "B4")
      (value "BMIS-205")
      (footprint "eagle-import:BMIS-205")
      (libsource (lib "eagle-import") (part "BMIS-205"))
    )
    (comp (ref "B5")
      (value "BMIS-205")
      (footprint "eagle-import:BMIS-205")
      (libsource (lib "eagle-import") (part "BMIS-205"))
    )
    (comp (ref "B6")
      (value "BMIS-205")
      (footprint "eagle-import:BMIS-205")
      (libsource (lib "eagle-import") (part "BMIS-205"))
    )
    (comp (ref "C58")
      (value "100nF")
      (footprint "eagle-import:C0603")
      (libsource (lib "eagle-import") (part "C-EUC0603"))
    )
    (comp (ref "C59")
      (value "100nF")
      (footprint "eagle-import:C0603")
      (libsource (lib "eagle-import") (part "C-EUC0603"))
    )
    (comp (ref "C60")
      (value "1µF")
      (footprint "eagle-import:C0603")
      (libsource (lib "eagle-import") (part "C-EUC0603"))
    )
    (comp (ref "C61")
      (value "1nF")
      (footprint "eagle-import:C0402")
      (libsource (lib "eagle-import") (part "C-EUC0402"))
    )
    (comp (ref "C62")
      (value "100pF")
      (footprint "eagle-import:C0402")
      (libsource (lib "eagle-import") (part "C-EUC0402"))
    )
    (comp (ref "C63")
      (value "1µF")
      (footprint "eagle-import:C0603")
      (libsource (lib "eagle-import") (part "C-EUC0603"))
    )
    (comp (ref "C64")
      (value "1nF")
      (footprint "eagle-import:C0402")
      (libsource (lib "eagle-import") (part "C-EUC0402"))
    )
    (comp (ref "C65")
      (value "100pF")
      (footprint "eagle-import:C0402")
      (libsource (lib "eagle-import") (part "C-EUC0402"))
    )
    (comp (ref "C66")
      (value "100nF")
      (footprint "eagle-import:C0603")
      (libsource (lib "eagle-import") (part "C-EUC0603"))
    )
    (comp (ref "C67")
      (value "22pF")
      (footprint "eagle-import:C0402")
      (libsource (lib "eagle-import") (part "C-EUC0402"))
    )
    (comp (ref "C68")
      (value "22pF")
      (footprint "eagle-import:C0402")
      (libsource (lib "eagle-import") (part "C-EUC0402"))
    )
    (comp (ref "C69")
      (value "22pF")
      (footprint "eagle-import:C0402")
      (libsource (lib "eagle-import") (part "C-EUC0402"))
    )
    (comp (ref "C70")
      (value "22pF")
      (footprint "eagle-import:C0402")
      (libsource (lib "eagle-import") (part "C-EUC0402"))
    )
    (comp (ref "C71")
      (value "22pF")
      (footprint "eagle-import:C0402")
      (libsource (lib "eagle-import") (part "C-EUC0402"))
    )
    (comp (ref "C72")
      (value "22pF")
      (footprint "eagle-import:C0402")
      (libsource (lib "eagle-import") (part "C-EUC0402"))
    )
    (comp (ref "C73")
      (value "100nF")
      (footprint "eagle-import:C0402")
      (libsource (lib "eagle-import") (part "C-EUC0402"))
    )
    (comp (ref "C74")
      (value "220pF")
      (footprint "eagle-import:C0402")
      (libsource (lib "eagle-import") (part "C-EUC0402"))
    )
    (comp (ref "C75")
      (value "10pF")
      (footprint "eagle-import:C0402")
      (libsource (lib "eagle-import") (part "C-EUC0402"))
    )
    (comp (ref "C76")
      (value "15pF")
      (footprint "eagle-import:C0402")
      (libsource (lib "eagle-import") (part "C-EUC0402"))
    )
    (comp (ref "C77")
      (value "10pF")
      (footprint "eagle-import:C0402")
      (libsource (lib "eagle-import") (part "C-EUC0402"))
    )
    (comp (ref "C78")
      (value "100nF")
      (footprint "eagle-import:C0603")
      (libsource (lib "eagle-import") (part "C-EUC0603"))
    )
    (comp (ref "C79")
      (value "100nF")
      (footprint "eagle-import:C0603")
      (libsource (lib "eagle-import") (part "C-EUC0603"))
    )
    (comp (ref "C80")
      (value "1µF")
      (footprint "eagle-import:C0603")
      (libsource (lib "eagle-import") (part "C-EUC0603"))
    )
    (comp (ref "C81")
      (value "1nF")
      (footprint "eagle-import:C0402")
      (libsource (lib "eagle-import") (part "C-EUC0402"))
    )
    (comp (ref "C82")
      (value "100pF")
      (footprint "eagle-import:C0402")
      (libsource (lib "eagle-import") (part "C-EUC0402"))
    )
    (comp (ref "C83")
      (value "100pF")
      (footprint "eagle-import:C0402")
      (libsource (lib "eagle-import") (part "C-EUC0402"))
    )
    (comp (ref "C84")
      (value "1nF")
      (footprint "eagle-import:C0402")
      (libsource (lib "eagle-import") (part "C-EUC0402"))
    )
    (comp (ref "C85")
      (value "1µF")
      (footprint "eagle-import:C0603")
      (libsource (lib "eagle-import") (part "C-EUC0603"))
    )
    (comp (ref "C86")
      (value "100nF")
      (footprint "eagle-import:C0603")
      (libsource (lib "eagle-import") (part "C-EUC0603"))
    )
    (comp (ref "C87")
      (value "22pF")
      (footprint "eagle-import:C0402")
      (libsource (lib "eagle-import") (part "C-EUC0402"))
    )
    (comp (ref "C88")
      (value "22pF")
      (footprint "eagle-import:C0402")
      (libsource (lib "eagle-import") (part "C-EUC0402"))
    )
    (comp (ref "C89")
      (value "22pF")
      (footprint "eagle-import:C0402")
      (libsource (lib "eagle-import") (part "C-EUC0402"))
    )
    (comp (ref "C90")
      (value "22pF")
      (footprint "eagle-import:C0402")
      (libsource (lib "eagle-import") (part "C-EUC0402"))
    )
    (comp (ref "C91")
      (value "22pF")
      (footprint "eagle-import:C0402")
      (libsource (lib "eagle-import") (part "C-EUC0402"))
    )
    (comp (ref "C92")
      (value "220pF")
      (footprint "eagle-import:C0402")
      (libsource (lib "eagle-import") (part "C-EUC0402"))
    )
    (comp (ref "C93")
      (value "10pF")
      (footprint "eagle-import:C0402")
      (libsource (lib "eagle-import") (part "C-EUC0402"))
    )
    (comp (ref "C94")
      (value "15pF")
      (footprint "eagle-import:C0402")
      (libsource (lib "eagle-import") (part "C-EUC0402"))
    )
    (comp (ref "C95")
      (value "10pF")
      (footprint "eagle-import:C0402")
      (libsource (lib "eagle-import") (part "C-EUC0402"))
    )
    (comp (ref "C96")
      (value "100nF")
      (footprint "eagle-import:C0603")
      (libsource (lib "eagle-import") (part "C-EUC0603"))
    )
    (comp (ref "C97")
      (value "100nF")
      (footprint "eagle-import:C0603")
      (libsource (lib "eagle-import") (part "C-EUC0603"))
    )
    (comp (ref "C98")
      (value "1µF")
      (footprint "eagle-import:C0603")
      (libsource (lib "eagle-import") (part "C-EUC0603"))
    )
    (comp (ref "C99")
      (value "1nF")
      (footprint "eagle-import:C0402")
      (libsource (lib "eagle-import") (part "C-EUC0402"))
    )
    (comp (ref "C100")
      (value "100pF")
      (footprint "eagle-import:C0402")
      (libsource (lib "eagle-import") (part "C-EUC0402"))
    )
    (comp (ref "C101")
      (value "1µF")
      (footprint "eagle-import:C0603")
      (libsource (lib "eagle-import") (part "C-EUC0603"))
    )
    (comp (ref "C102")
      (value "1nF")
      (footprint "eagle-import:C0402")
      (libsource (lib "eagle-import") (part "C-EUC0402"))
    )
    (comp (ref "C103")
      (value "100pF")
      (footprint "eagle-import:C0402")
      (libsource (lib "eagle-import") (part "C-EUC0402"))
    )
    (comp (ref "C104")
      (value "22pF")
      (footprint "eagle-import:C0402")
      (libsource (lib "eagle-import") (part "C-EUC0402"))
    )
    (comp (ref "C105")
      (value "22pF")
      (footprint "eagle-import:C0402")
      (libsource (lib "eagle-import") (part "C-EUC0402"))
    )
    (comp (ref "C106")
      (value "22pF")
      (footprint "eagle-import:C0402")
      (libsource (lib "eagle-import") (part "C-EUC0402"))
    )
    (comp (ref "C107")
      (value "22pF")
      (footprint "eagle-import:C0402")
      (libsource (lib "eagle-import") (part "C-EUC0402"))
    )
    (comp (ref "D8")
      (value "SMF5.0AT1")
      (footprint "eagle-import:SOD123FL")
      (libsource (lib "eagle-import") (part "SMF5.0AT1"))
    )
    (comp (ref "F1")
      (value "SAW_FILTER_33F")
      (footprint "eagle-import:BOITIER_3-3")
      (libsource (lib "eagle-import") (part "SAW_FILTER_33F"))
    )
    (comp (ref "F2")
      (value "SAW_FILTER_33F")
      (footprint "eagle-import:BOITIER_3-3")
      (libsource (lib "eagle-import") (part "SAW_FILTER_33F"))
    )
    (comp (ref "F3")
      (value "SAW_FILTER_33F")
      (footprint "eagle-import:BOITIER_3-3")
      (libsource (lib "eagle-import") (part "SAW_FILTER_33F"))
    )
    (comp (ref "IC2")
      (value "HMC474MP86")
      (footprint "eagle-import:VV105")
      (libsource (lib "eagle-import") (part "HMC474MP86"))
    )
    (comp (ref "IC3")
      (value "HMC474MP86")
      (footprint "eagle-import:VV105")
      (libsource (lib "eagle-import") (part "HMC474MP86"))
    )
    (comp (ref "IC4")
      (value "HMC349MS8G")
      (footprint "eagle-import:SMT-MS8G")
      (libsource (lib "eagle-import") (part "HMC349MS8G"))
    )
    (comp (ref "IC5")
      (value "HMC349MS8G")
      (footprint "eagle-import:SMT-MS8G")
      (libsource (lib "eagle-import") (part "HMC349MS8G"))
    )
    (comp (ref "IC6")
      (value "HMC349MS8G")
      (footprint "eagle-import:SMT-MS8G")
      (libsource (lib "eagle-import") (part "HMC349MS8G"))
    )
    (comp (ref "IC7")
      (value "SGA-3563Z")
      (footprint "eagle-import:SOT363")
      (libsource (lib "eagle-import") (part "SGA-3563Z"))
    )
    (comp (ref "IC8")
      (value "SGA-3563Z")
      (footprint "eagle-import:SOT363")
      (libsource (lib "eagle-import") (part "SGA-3563Z"))
    )
    (comp (ref "IC9")
      (value "HMC474MP86")
      (footprint "eagle-import:VV105")
      (libsource (lib "eagle-import") (part "HMC474MP86"))
    )
    (comp (ref "IC10")
      (value "HMC474MP86")
      (footprint "eagle-import:VV105")
      (libsource (lib "eagle-import") (part "HMC474MP86"))
    )
    (comp (ref "J2")
      (value "SMA-BORDMIN")
      (footprint "eagle-import:SMA_BORDMIN")
      (libsource (lib "eagle-import") (part "SMA-BORDMIN"))
    )
    (comp (ref "L3")
      (value "L_0402")
      (footprint "eagle-import:0402")
      (libsource (lib "eagle-import") (part "L_0402"))
    )
    (comp (ref "L4")
      (value "L_0402")
      (footprint "eagle-import:0402")
      (libsource (lib "eagle-import") (part "L_0402"))
    )
    (comp (ref "L5")
      (value "100nH")
      (footprint "eagle-import:0603")
      (libsource (lib "eagle-import") (part "L_0603"))
    )
    (comp (ref "L6")
      (value "100nH")
      (footprint "eagle-import:0603")
      (libsource (lib "eagle-import") (part "L_0603"))
    )
    (comp (ref "L7")
      (value "BLM15BB221SN1")
      (footprint "eagle-import:0402")
      (libsource (lib "eagle-import") (part "L_0402"))
    )
    (comp (ref "L8")
      (value "BLM15BB221SN1")
      (footprint "eagle-import:0402")
      (libsource (lib "eagle-import") (part "L_0402"))
    )
    (comp (ref "L9")
      (value "15nH")
      (footprint "eagle-import:0603")
      (libsource (lib "eagle-import") (part "L_0603"))
    )
    (comp (ref "L10")
      (value "15nH")
      (footprint "eagle-import:0603")
      (libsource (lib "eagle-import") (part "L_0603"))
    )
    (comp (ref "L11")
      (value "BLM15BB221SN1")
      (footprint "eagle-import:0402")
      (libsource (lib "eagle-import") (part "L_0402"))
    )
    (comp (ref "L12")
      (value "1,8nH")
      (footprint "eagle-import:0603")
      (libsource (lib "eagle-import") (part "L_0603"))
    )
    (comp (ref "L13")
      (value "BLM15BB221SN1")
      (footprint "eagle-import:0402")
      (libsource (lib "eagle-import") (part "L_0402"))
    )
    (comp (ref "L14")
      (value "68nH")
      (footprint "eagle-import:0603")
      (libsource (lib "eagle-import") (part "L_0603"))
    )
    (comp (ref "L15")
      (value "68nH")
      (footprint "eagle-import:0603")
      (libsource (lib "eagle-import") (part "L_0603"))
    )
    (comp (ref "L16")
      (value "15nH")
      (footprint "eagle-import:0603")
      (libsource (lib "eagle-import") (part "L_0603"))
    )
    (comp (ref "L17")
      (value "15nH")
      (footprint "eagle-import:0603")
      (libsource (lib "eagle-import") (part "L_0603"))
    )
    (comp (ref "L18")
      (value "1,8nH")
      (footprint "eagle-import:0603")
      (libsource (lib "eagle-import") (part "L_0603"))
    )
    (comp (ref "L19")
      (value "100nH")
      (footprint "eagle-import:0603")
      (libsource (lib "eagle-import") (part "L_0603"))
    )
    (comp (ref "L20")
      (value "100nH")
      (footprint "eagle-import:0603")
      (libsource (lib "eagle-import") (part "L_0603"))
    )
    (comp (ref "R38")
      (value "18")
      (footprint "eagle-import:R0603")
      (libsource (lib "eagle-import") (part "R-US_R0603"))
    )
    (comp (ref "R39")
      (value "18")
      (footprint "eagle-import:R0603")
      (libsource (lib "eagle-import") (part "R-US_R0603"))
    )
    (comp (ref "R40")
      (value "50")
      (footprint "eagle-import:R0603")
      (libsource (lib "eagle-import") (part "R-US_R0603"))
    )
    (comp (ref "R41")
      (value "51")
      (footprint "eagle-import:R0603")
      (libsource (lib "eagle-import") (part "R-US_R0603"))
    )
    (comp (ref "R42")
      (value "51")
      (footprint "eagle-import:R0603")
      (libsource (lib "eagle-import") (part "R-US_R0603"))
    )
    (comp (ref "R43")
      (value "50")
      (footprint "eagle-import:R0402")
      (libsource (lib "eagle-import") (part "R-US_R0402"))
    )
    (comp (ref "R44")
      (value "50")
      (footprint "eagle-import:R0402")
      (libsource (lib "eagle-import") (part "R-US_R0402"))
    )
    (comp (ref "R45")
      (value "50")
      (footprint "eagle-import:R0402")
      (libsource (lib "eagle-import") (part "R-US_R0402"))
    )
    (comp (ref "R46")
      (value "50")
      (footprint "eagle-import:R0402")
      (libsource (lib "eagle-import") (part "R-US_R0402"))
    )
    (comp (ref "R47")
      (value "18")
      (footprint "eagle-import:R0603")
      (libsource (lib "eagle-import") (part "R-US_R0603"))
    )
    (comp (ref "R48")
      (value "18")
      (footprint "eagle-import:R0603")
      (libsource (lib "eagle-import") (part "R-US_R0603"))
    )
    (comp (ref "SAW1")
      (value "SAW_DBLPORT")
      (footprint "eagle-import:BOITIER_5-5")
      (libsource (lib "eagle-import") (part "SAW_DBLPORT"))
    )
    (comp (ref "SAW2")
      (value "SAW_DBLPORT")
      (footprint "eagle-import:BOITIER_5-5")
      (libsource (lib "eagle-import") (part "SAW_DBLPORT"))
    )
    (comp (ref "SAW3")
      (value "SAW_DBLPORT")
      (footprint "eagle-import:BOITIER_5-5")
      (libsource (lib "eagle-import") (part "SAW_DBLPORT"))
    )
  )
  (nets
    (net (code "1") (name "+3V3") (class "Default")
      (node (ref "ADM1") (pin "3") (pinfunction "C_3") (pintype "passive"))
      (node (ref "C1") (pin "1") (pinfunction "1_1") (pintype "passive"))
      (node (ref "C111") (pin "2") (pinfunction "2_2") (pintype "passive"))
      (node (ref "C114") (pin "2") (pinfunction "2_2") (pintype "passive"))
      (node (ref "C2") (pin "1") (pinfunction "1_1") (pintype "passive"))
      (node (ref "C23") (pin "1") (pinfunction "1_1") (pintype "passive"))
      (node (ref "C3") (pin "1") (pinfunction "1_1") (pintype "passive"))
      (node (ref "C4") (pin "1") (pinfunction "1_1") (pintype "passive"))
      (node (ref "C5") (pin "1") (pinfunction "1_1") (pintype "passive"))
      (node (ref "C6") (pin "1") (pinfunction "1_1") (pintype "passive"))
      (node (ref "DZ1") (pin "A1") (pinfunction "A_A1") (pintype "passive"))
      (node (ref "IC1") (pin "4") (pinfunction "VCCIO_4") (pintype "power_in"))
      (node (ref "L21COILCRAFT_LPS6225-103") (pin "P$2") (pinfunction "2_P$2") (pintype "passive"))
      (node (ref "R4") (pin "2") (pinfunction "2_2") (pintype "passive"))
      (node (ref "R49") (pin "2") (pinfunction "2_2") (pintype "passive"))
      (node (ref "R5") (pin "1") (pinfunction "1_1") (pintype "passive"))
      (node (ref "U1") (pin "13") (pinfunction "VDDA_13") (pintype "power_in"))
      (node (ref "U1") (pin "19") (pinfunction "VDD_4_19") (pintype "power_in"))
      (node (ref "U1") (pin "32") (pinfunction "VDD_1_32") (pintype "power_in"))
      (node (ref "U1") (pin "48") (pinfunction "VDD_2_48") (pintype "power_in"))
      (node (ref "U1") (pin "64") (pinfunction "VDD_3_64") (pintype "power_in"))
      (node (ref "U2") (pin "49") (pinfunction "DVDD_I/O_49") (pintype "power_in"))
    )
    (net (code "2") (name "+5V") (class "Default")
      (node (ref "C110") (pin "2") (pinfunction "2_2") (pintype "passive"))
      (node (ref "C112") (pin "2") (pinfunction "2_2") (pintype "passive"))
      (node (ref "C35") (pin "1") (pinfunction "1_1") (pintype "passive"))
      (node (ref "C36") (pin "1") (pinfunction "1_1") (pintype "passive"))
      (node (ref "C48") (pin "2") (pinfunction "2_2") (pintype "passive"))
      (node (ref "C58") (pin "1") (pinfunction "1_1") (pintype "passive"))
      (node (ref "C59") (pin "1") (pinfunction "1_1") (pintype "passive"))
      (node (ref "C78") (pin "1") (pinfunction "1_1") (pintype "passive"))
      (node (ref "C79") (pin "1") (pinfunction "1_1") (pintype "passive"))
      (node (ref "C96") (pin "1") (pinfunction "1_1") (pintype "passive"))
      (node (ref "C97") (pin "1") (pinfunction "1_1") (pintype "passive"))
      (node (ref "DZ1") (pin "A2") (pinfunction "A_A2") (pintype "passive"))
      (node (ref "IC11") (pin "1") (pinfunction "IN_1") (pintype "input"))
      (node (ref "IC11") (pin "3") (pinfunction "ON_3") (pintype "input"))
      (node (ref "L11") (pin "2") (pinfunction "2_2") (pintype "passive"))
      (node (ref "L22COILCRAFT_LPS6225-103") (pin "P$2") (pinfunction "2_P$2") (pintype "passive"))
      (node (ref "L3") (pin "2") (pinfunction "2_2") (pintype "passive"))
      (node (ref "L7") (pin "2") (pinfunction "2_2") (pintype "passive"))
      (node (ref "R28") (pin "2") (pinfunction "2_2") (pintype "passive"))
      (node (ref "R38") (pin "2") (pinfunction "2_2") (pintype "passive"))
      (node (ref "R39") (pin "2") (pinfunction "2_2") (pintype "passive"))
      (node (ref "R41") (pin "2") (pinfunction "2_2") (pintype "passive"))
      (node (ref "R42") (pin "2") (pinfunction "2_2") (pintype "passive"))
      (node (ref "R47") (pin "2") (pinfunction "2_2") (pintype "passive"))
      (node (ref "R48") (pin "2") (pinfunction "2_2") (pintype "passive"))
      (node (ref "R53") (pin "2") (pinfunction "2_2") (pintype "passive"))
      (node (ref "U5") (pin "13") (pinfunction "VPOS_13") (pintype "power_in"))
    )
    (net (code "3") (name "3V3_AOP") (class "Default")
      (node (ref "C121") (pin "2") (pinfunction "2_2") (pintype "passive"))
      (node (ref "IC11") (pin "5") (pinfunction "OUT_5") (pintype "output"))
      (node (ref "R20") (pin "2") (pinfunction "2_2") (pintype "passive"))
      (node (ref "R25") (pin "2") (pinfunction "2_2") (pintype "passive"))
      (node (ref "R27") (pin "2") (pinfunction "2_2") (pintype "passive"))
      (node (ref "R34") (pin "2") (pinfunction "2_2") (pintype "passive"))
      (node (ref "U3") (pin "5") (pinfunction "VDD_5") (pintype "power_in"))
    )
    (net (code "4") (name "CBUS1") (class "Default")
      (node (ref "IC1") (pin "22") (pinfunction "CBUS1_22") (pintype "bidirectional"))
      (node (ref "JP1") (pin "2") (pinfunction "2_2") (pintype "passive"))
      (node (ref "R7") (pin "2") (pinfunction "2_2") (pintype "passive"))
      (node (ref "U1") (pin "60") (pinfunction "BOOT0_60") (pintype "passive"))
    )
    (net (code "5") (name "CBUS2") (class "Default")
      (node (ref "IC1") (pin "13") (pinfunction "CBUS2_13") (pintype "bidirectional"))
      (node (ref "Q2") (pin "1") (pinfunction "B_1") (pintype "passive"))
    )
    (net (code "6") (name "COM_1.8") (class "Default")
      (node (ref "R56") (pin "1") (pinfunction "1_1") (pintype "passive"))
      (node (ref "U1") (pin "61") (pinfunction "PB8_61") (pintype "bidirectional"))
      (node (ref "U12") (pin "4") (pinfunction "EN_4") (pintype "input"))
    )
    (net (code "7") (name "COM_5V") (class "Default")
      (node (ref "R52") (pin "1") (pinfunction "1_1") (pintype "passive"))
      (node (ref "U1") (pin "59") (pinfunction "PB7_59") (pintype "power_in"))
      (node (ref "U11") (pin "4") (pinfunction "EN_4") (pintype "input"))
    )
    (net (code "8") (name "CS_DDS") (class "Default")
      (node (ref "U1") (pin "46") (pinfunction "PA13_46") (pintype "bidirectional"))
      (node (ref "U2") (pin "47") (pinfunction "~{CS}_47") (pintype "input"))
    )
    (net (code "9") (name "CTL_DUPL") (class "Default")
      (node (ref "L8") (pin "2") (pinfunction "2_2") (pintype "passive"))
      (node (ref "U1") (pin "30") (pinfunction "PB11_30") (pintype "bidirectional"))
    )
    (net (code "10") (name "CTL_EM") (class "Default")
      (node (ref "L4") (pin "2") (pinfunction "2_2") (pintype "passive"))
      (node (ref "U1") (pin "29") (pinfunction "PB10_29") (pintype "bidirectional"))
    )
    (net (code "11") (name "CTL_RECEPT") (class "Default")
      (node (ref "L13") (pin "2") (pinfunction "2_2") (pintype "passive"))
      (node (ref "U1") (pin "62") (pinfunction "PB9_62") (pintype "bidirectional"))
    )
    (net (code "12") (name "DDS_V0") (class "Default")
      (node (ref "C104") (pin "1") (pinfunction "1_1") (pintype "passive"))
      (node (ref "DDS_V0") (pin "1") (pinfunction "P_1") (pintype "passive"))
      (node (ref "TR2") (pin "P6") (pinfunction "P2_P6") (pintype "passive"))
    )
    (net (code "13") (name "DDS_V1") (class "Default")
      (node (ref "C71") (pin "1") (pinfunction "1_1") (pintype "passive"))
      (node (ref "DDS_V1") (pin "1") (pinfunction "P_1") (pintype "passive"))
      (node (ref "TR1") (pin "P6") (pinfunction "P2_P6") (pintype "passive"))
    )
    (net (code "14") (name "GND") (class "Default")
      (node (ref "ADM1") (pin "1") (pinfunction "B_1") (pintype "passive"))
      (node (ref "B3") (pin "P$1") (pinfunction "GND_P$1") (pintype "bidirectional"))
      (node (ref "B3") (pin "P$10") (pinfunction "GND_P$10") (pintype "bidirectional"))
      (node (ref "B3") (pin "P$11") (pinfunction "GND_P$11") (pintype "bidirectional"))
      (node (ref "B3") (pin "P$12") (pinfunction "GND_P$12") (pintype "bidirectional"))
      (node (ref "B3") (pin "P$2") (pinfunction "GND_P$2") (pintype "bidirectional"))
      (node (ref "B3") (pin "P$3") (pinfunction "GND_P$3") (pintype "bidirectional"))
      (node (ref "B3") (pin "P$4") (pinfunction "GND_P$4") (pintype "bidirectional"))
      (node (ref "B3") (pin "P$5") (pinfunction "GND_P$5") (pintype "bidirectional"))
      (node (ref "B3") (pin "P$6") (pinfunction "GND_P$6") (pintype "bidirectional"))
      (node (ref "B3") (pin "P$7") (pinfunction "GND_P$7") (pintype "bidirectional"))
      (node (ref "B3") (pin "P$8") (pinfunction "GND_P$8") (pintype "bidirectional"))
      (node (ref "B3") (pin "P$9") (pinfunction "GND_P$9") (pintype "bidirectional"))
      (node (ref "B4") (pin "P$1") (pinfunction "GND_P$1") (pintype "bidirectional"))
      (node (ref "B4") (pin "P$10") (pinfunction "GND_P$10") (pintype "bidirectional"))
      (node (ref "B4") (pin "P$11") (pinfunction "GND_P$11") (pintype "bidirectional"))
      (node (ref "B4") (pin "P$12") (pinfunction "GND_P$12") (pintype "bidirectional"))
      (node (ref "B4") (pin "P$13") (pinfunction "GND_P$13") (pintype "bidirectional"))
      (node (ref "B4") (pin "P$14") (pinfunction "GND_P$14") (pintype "bidirectional"))
      (node (ref "B4") (pin "P$15") (pinfunction "GND_P$15") (pintype "bidirectional"))
      (node (ref "B4") (pin "P$16") (pinfunction "GND_P$16") (pintype "bidirectional"))
      (node (ref "B4") (pin "P$17") (pinfunction "GND_P$17") (pintype "bidirectional"))
      (node (ref "B4") (pin "P$18") (pinfunction "GND_P$18") (pintype "bidirectional"))
      (node (ref "B4") (pin "P$19") (pinfunction "GND_P$19") (pintype "bidirectional"))
      (node (ref "B4") (pin "P$2") (pinfunction "GND_P$2") (pintype "bidirectional"))
      (node (ref "B4") (pin "P$20") (pinfunction "GND_P$20") (pintype "bidirectional"))
      (node (ref "B4") (pin "P$21") (pinfunction "GND_P$21") (pintype "bidirectional"))
      (node (ref "B4") (pin "P$22") (pinfunction "GND_P$22") (pintype "bidirectional"))
      (node (ref "B4") (pin "P$23") (pinfunction "GND_P$23") (pintype "bidirectional"))
      (node (ref "B4") (pin "P$24") (pinfunction "GND_P$24") (pintype "bidirectional"))
      (node (ref "B4") (pin "P$3") (pinfunction "GND_P$3") (pintype "bidirectional"))
      (node (ref "B4") (pin "P$4") (pinfunction "GND_P$4") (pintype "bidirectional"))
      (node (ref "B4") (pin "P$5") (pinfunction "GND_P$5") (pintype "bidirectional"))
      (node (ref "B4") (pin "P$6") (pinfunction "GND_P$6") (pintype "bidirectional"))
      (node (ref "B4") (pin "P$7") (pinfunction "GND_P$7") (pintype "bidirectional"))
      (node (ref "B4") (pin "P$8") (pinfunction "GND_P$8") (pintype "bidirectional"))
      (node (ref "B4") (pin "P$9") (pinfunction "GND_P$9") (pintype "bidirectional"))
      (node (ref "B5") (pin "P$1") (pinfunction "GND_P$1") (pintype "bidirectional"))
      (node (ref "B5") (pin "P$10") (pinfunction "GND_P$10") (pintype "bidirectional"))
      (node (ref "B5") (pin "P$11") (pinfunction "GND_P$11") (pintype "bidirectional"))
      (node (ref "B5") (pin "P$12") (pinfunction "GND_P$12") (pintype "bidirectional"))
      (node (ref "B5") (pin "P$13") (pinfunction "GND_P$13") (pintype "bidirectional"))
      (node (ref "B5") (pin "P$14") (pinfunction "GND_P$14") (pintype "bidirectional"))
      (node (ref "B5") (pin "P$15") (pinfunction "GND_P$15") (pintype "bidirectional"))
      (node (ref "B5") (pin "P$16") (pinfunction "GND_P$16") (pintype "bidirectional"))
      (node (ref "B5") (pin "P$17") (pinfunction "GND_P$17") (pintype "bidirectional"))
      (node (ref "B5") (pin "P$18") (pinfunction "GND_P$18") (pintype "bidirectional"))
      (node (ref "B5") (pin "P$19") (pinfunction "GND_P$19") (pintype "bidirectional"))
      (node (ref "B5") (pin "P$2") (pinfunction "GND_P$2") (pintype "bidirectional"))
      (node (ref "B5") (pin "P$20") (pinfunction "GND_P$20") (pintype "bidirectional"))
      (node (ref "B5") (pin "P$21") (pinfunction "GND_P$21") (pintype "bidirectional"))
      (node (ref "B5") (pin "P$22") (pinfunction "GND_P$22") (pintype "bidirectional"))
      (node (ref "B5") (pin "P$23") (pinfunction "GND_P$23") (pintype "bidirectional"))
      (node (ref "B5") (pin "P$24") (pinfunction "GND_P$24") (pintype "bidirectional"))
      (node (ref "B5") (pin "P$3") (pinfunction "GND_P$3") (pintype "bidirectional"))
      (node (ref "B5") (pin "P$4") (pinfunction "GND_P$4") (pintype "bidirectional"))
      (node (ref "B5") (pin "P$5") (pinfunction "GND_P$5") (pintype "bidirectional"))
      (node (ref "B5") (pin "P$6") (pinfunction "GND_P$6") (pintype "bidirectional"))
      (node (ref "B5") (pin "P$7") (pinfunction "GND_P$7") (pintype "bidirectional"))
      (node (ref "B5") (pin "P$8") (pinfunction "GND_P$8") (pintype "bidirectional"))
      (node (ref "B5") (pin "P$9") (pinfunction "GND_P$9") (pintype "bidirectional"))
      (node (ref "B6") (pin "P$1") (pinfunction "GND_P$1") (pintype "bidirectional"))
      (node (ref "B6") (pin "P$10") (pinfunction "GND_P$10") (pintype "bidirectional"))
      (node (ref "B6") (pin "P$11") (pinfunction "GND_P$11") (pintype "bidirectional"))
      (node (ref "B6") (pin "P$12") (pinfunction "GND_P$12") (pintype "bidirectional"))
      (node (ref "B6") (pin "P$13") (pinfunction "GND_P$13") (pintype "bidirectional"))
      (node (ref "B6") (pin "P$14") (pinfunction "GND_P$14") (pintype "bidirectional"))
      (node (ref "B6") (pin "P$15") (pinfunction "GND_P$15") (pintype "bidirectional"))
      (node (ref "B6") (pin "P$16") (pinfunction "GND_P$16") (pintype "bidirectional"))
      (node (ref "B6") (pin "P$17") (pinfunction "GND_P$17") (pintype "bidirectional"))
      (node (ref "B6") (pin "P$18") (pinfunction "GND_P$18") (pintype "bidirectional"))
      (node (ref "B6") (pin "P$19") (pinfunction "GND_P$19") (pintype "bidirectional"))
      (node (ref "B6") (pin "P$2") (pinfunction "GND_P$2") (pintype "bidirectional"))
      (node (ref "B6") (pin "P$20") (pinfunction "GND_P$20") (pintype "bidirectional"))
      (node (ref "B6") (pin "P$21") (pinfunction "GND_P$21") (pintype "bidirectional"))
      (node (ref "B6") (pin "P$22") (pinfunction "GND_P$22") (pintype "bidirectional"))
      (node (ref "B6") (pin "P$23") (pinfunction "GND_P$23") (pintype "bidirectional"))
      (node (ref "B6") (pin "P$24") (pinfunction "GND_P$24") (pintype "bidirectional"))
      (node (ref "B6") (pin "P$3") (pinfunction "GND_P$3") (pintype "bidirectional"))
      (node (ref "B6") (pin "P$4") (pinfunction "GND_P$4") (pintype "bidirectional"))
      (node (ref "B6") (pin "P$5") (pinfunction "GND_P$5") (pintype "bidirectional"))
      (node (ref "B6") (pin "P$6") (pinfunction "GND_P$6") (pintype "bidirectional"))
      (node (ref "B6") (pin "P$7") (pinfunction "GND_P$7") (pintype "bidirectional"))
      (node (ref "B6") (pin "P$8") (pinfunction "GND_P$8") (pintype "bidirectional"))
      (node (ref "B6") (pin "P$9") (pinfunction "GND_P$9") (pintype "bidirectional"))
      (node (ref "C1") (pin "2") (pinfunction "2_2") (pintype "passive"))
      (node (ref "C10") (pin "2") (pinfunction "2_2") (pintype "passive"))
      (node (ref "C100") (pin "2") (pinfunction "2_2") (pintype "passive"))
      (node (ref "C101") (pin "2") (pinfunction "2_2") (pintype "passive"))
      (node (ref "C102") (pin "2") (pinfunction "2_2") (pintype "passive"))
      (node (ref "C103") (pin "2") (pinfunction "2_2") (pintype "passive"))
      (node (ref "C108") (pin "1") (pinfunction "1_1") (pintype "passive"))
      (node (ref "C109") (pin "1") (pinfunction "1_1") (pintype "passive"))
      (node (ref "C11") (pin "2") (pinfunction "2_2") (pintype "passive"))
      (node (ref "C110") (pin "1") (pinfunction "1_1") (pintype "passive"))
      (node (ref "C111") (pin "1") (pinfunction "1_1") (pintype "passive"))
      (node (ref "C112") (pin "1") (pinfunction "1_1") (pintype "passive"))
      (node (ref "C114") (pin "1") (pinfunction "1_1") (pintype "passive"))
      (node (ref "C115") (pin "1") (pinfunction "1_1") (pintype "passive"))
      (node (ref "C116") (pin "1") (pinfunction "1_1") (pintype "passive"))
      (node (ref "C118") (pin "1") (pinfunction "1_1") (pintype "passive"))
      (node (ref "C12") (pin "2") (pinfunction "2_2") (pintype "passive"))
      (node (ref "C120") (pin "-") (pinfunction "-_-") (pintype "passive"))
      (node (ref "C121") (pin "1") (pinfunction "1_1") (pintype "passive"))
      (node (ref "C13") (pin "2") (pinfunction "2_2") (pintype "passive"))
      (node (ref "C14") (pin "2") (pinfunction "2_2") (pintype "passive"))
      (node (ref "C15") (pin "2") (pinfunction "2_2") (pintype "passive"))
      (node (ref "C16") (pin "2") (pinfunction "2_2") (pintype "passive"))
      (node (ref "C17") (pin "2") (pinfunction "2_2") (pintype "passive"))
      (node (ref "C18") (pin "2") (pinfunction "2_2") (pintype "passive"))
      (node (ref "C19") (pin "2") (pinfunction "2_2") (pintype "passive"))
      (node (ref "C2") (pin "2") (pinfunction "2_2") (pintype "passive"))
      (node (ref "C20") (pin "2") (pinfunction "2_2") (pintype "passive"))
      (node (ref "C21") (pin "2") (pinfunction "2_2") (pintype "passive"))
      (node (ref "C22") (pin "2") (pinfunction "2_2") (pintype "passive"))
      (node (ref "C23") (pin "2") (pinfunction "2_2") (pintype "passive"))
      (node (ref "C24") (pin "2") (pinfunction "2_2") (pintype "passive"))
      (node (ref "C25") (pin "2") (pinfunction "2_2") (pintype "passive"))
      (node (ref "C26") (pin "2") (pinfunction "2_2") (pintype "passive"))
      (node (ref "C27") (pin "2") (pinfunction "2_2") (pintype "passive"))
      (node (ref "C28") (pin "2") (pinfunction "2_2") (pintype "passive"))
      (node (ref "C29") (pin "2") (pinfunction "2_2") (pintype "passive"))
      (node (ref "C3") (pin "2") (pinfunction "2_2") (pintype "passive"))
      (node (ref "C31") (pin "2") (pinfunction "2_2") (pintype "passive"))
      (node (ref "C32") (pin "2") (pinfunction "2_2") (pintype "passive"))
      (node (ref "C33") (pin "2") (pinfunction "2_2") (pintype "passive"))
      (node (ref "C34") (pin "2") (pinfunction "2_2") (pintype "passive"))
      (node (ref "C35") (pin "2") (pinfunction "2_2") (pintype "passive"))
      (node (ref "C36") (pin "2") (pinfunction "2_2") (pintype "passive"))
      (node (ref "C4") (pin "2") (pinfunction "2_2") (pintype "passive"))
      (node (ref "C40") (pin "2") (pinfunction "2_2") (pintype "passive"))
      (node (ref "C41") (pin "2") (pinfunction "2_2") (pintype "passive"))
      (node (ref "C42") (pin "2") (pinfunction "2_2") (pintype "passive"))
      (node (ref "C43") (pin "2") (pinfunction "2_2") (pintype "passive"))
      (node (ref "C44") (pin "2") (pinfunction "2_2") (pintype "passive"))
      (node (ref "C45") (pin "2") (pinfunction "2_2") (pintype "passive"))
      (node (ref "C46") (pin "2") (pinfunction "2_2") (pintype "passive"))
      (node (ref "C47") (pin "2") (pinfunction "2_2") (pintype "passive"))
      (node (ref "C48") (pin "1") (pinfunction "1_1") (pintype "passive"))
      (node (ref "C49") (pin "1") (pinfunction "1_1") (pintype "passive"))
      (node (ref "C5") (pin "2") (pinfunction "2_2") (pintype "passive"))
      (node (ref "C50") (pin "1") (pinfunction "1_1") (pintype "passive"))
      (node (ref "C51") (pin "1") (pinfunction "1_1") (pintype "passive"))
      (node (ref "C52") (pin "2") (pinfunction "2_2") (pintype "passive"))
      (node (ref "C54") (pin "2") (pinfunction "2_2") (pintype "passive"))
      (node (ref "C55") (pin "2") (pinfunction "2_2") (pintype "passive"))
      (node (ref "C57") (pin "2") (pinfunction "2_2") (pintype "passive"))
      (node (ref "C58") (pin "2") (pinfunction "2_2") (pintype "passive"))
      (node (ref "C59") (pin "2") (pinfunction "2_2") (pintype "passive"))
      (node (ref "C6") (pin "2") (pinfunction "2_2") (pintype "passive"))
      (node (ref "C60") (pin "2") (pinfunction "2_2") (pintype "passive"))
      (node (ref "C61") (pin "2") (pinfunction "2_2") (pintype "passive"))
      (node (ref "C62") (pin "2") (pinfunction "2_2") (pintype "passive"))
      (node (ref "C63") (pin "2") (pinfunction "2_2") (pintype "passive"))
      (node (ref "C64") (pin "2") (pinfunction "2_2") (pintype "passive"))
      (node (ref "C65") (pin "2") (pinfunction "2_2") (pintype "passive"))
      (node (ref "C66") (pin "2") (pinfunction "2_2") (pintype "passive"))
      (node (ref "C7") (pin "2") (pinfunction "2_2") (pintype "passive"))
      (node (ref "C73") (pin "2") (pinfunction "2_2") (pintype "passive"))
      (node (ref "C75") (pin "2") (pinfunction "2_2") (pintype "passive"))
      (node (ref "C77") (pin "2") (pinfunction "2_2") (pintype "passive"))
      (node (ref "C78") (pin "2") (pinfunction "2_2") (pintype "passive"))
      (node (ref "C79") (pin "2") (pinfunction "2_2") (pintype "passive"))
      (node (ref "C8") (pin "2") (pinfunction "2_2") (pintype "passive"))
      (node (ref "C80") (pin "2") (pinfunction "2_2") (pintype "passive"))
      (node (ref "C81") (pin "2") (pinfunction "2_2") (pintype "passive"))
      (node (ref "C82") (pin "2") (pinfunction "2_2") (pintype "passive"))
      (node (ref "C83") (pin "2") (pinfunction "2_2") (pintype "passive"))
      (node (ref "C84") (pin "2") (pinfunction "2_2") (pintype "passive"))
      (node (ref "C85") (pin "2") (pinfunction "2_2") (pintype "passive"))
      (node (ref "C86") (pin "2") (pinfunction "2_2") (pintype "passive"))
      (node (ref "C9") (pin "2") (pinfunction "2_2") (pintype "passive"))
      (node (ref "C93") (pin "2") (pinfunction "2_2") (pintype "passive"))
      (node (ref "C95") (pin "2") (pinfunction "2_2") (pintype "passive"))
      (node (ref "C96") (pin "2") (pinfunction "2_2") (pintype "passive"))
      (node (ref "C97") (pin "2") (pinfunction "2_2") (pintype "passive"))
      (node (ref "C98") (pin "2") (pinfunction "2_2") (pintype "passive"))
      (node (ref "C99") (pin "2") (pinfunction "2_2") (pintype "passive"))
      (node (ref "D1") (pin "K") (pinfunction "K_K") (pintype "passive"))
      (node (ref "D2") (pin "A") (pinfunction "A_A") (pintype "passive"))
      (node (ref "D3") (pin "A") (pinfunction "A_A") (pintype "passive"))
      (node (ref "D4") (pin "A") (pinfunction "A_A") (pintype "passive"))
      (node (ref "D5") (pin "A") (pinfunction "A_A") (pintype "passive"))
      (node (ref "D6") (pin "A") (pinfunction "A_A") (pintype "passive"))
      (node (ref "D7") (pin "A") (pinfunction "A_A") (pintype "passive"))
      (node (ref "D8") (pin "A") (pinfunction "A_A") (pintype "passive"))
      (node (ref "F1") (pin "P$1") (pinfunction "P$3_P$1") (pintype "bidirectional"))
      (node (ref "F2") (pin "P$1") (pinfunction "P$3_P$1") (pintype "bidirectional"))
      (node (ref "F3") (pin "P$1") (pinfunction "P$3_P$1") (pintype "bidirectional"))
      (node (ref "IC1") (pin "18") (pinfunction "GND_18") (pintype "power_in"))
      (node (ref "IC1") (pin "21") (pinfunction "GND_21") (pintype "power_in"))
      (node (ref "IC1") (pin "25") (pinfunction "GND_25") (pintype "power_in"))
      (node (ref "IC1") (pin "26") (pinfunction "TEST_26") (pintype "input"))
      (node (ref "IC1") (pin "7") (pinfunction "GND_7") (pintype "power_in"))
      (node (ref "IC10") (pin "2") (pinfunction "V_1_2") (pintype "bidirectional"))
      (node (ref "IC10") (pin "4") (pinfunction "V_2_4") (pintype "bidirectional"))
      (node (ref "IC11") (pin "2") (pinfunction "GND_2") (pintype "power_in"))
      (node (ref "IC2") (pin "2") (pinfunction "V_1_2") (pintype "bidirectional"))
      (node (ref "IC2") (pin "4") (pinfunction "V_2_4") (pintype "bidirectional"))
      (node (ref "IC3") (pin "2") (pinfunction "V_1_2") (pintype "bidirectional"))
      (node (ref "IC3") (pin "4") (pinfunction "V_2_4") (pintype "bidirectional"))
      (node (ref "IC4") (pin "P$4") (pinfunction "EN_P$4") (pintype "bidirectional"))
      (node (ref "IC4") (pin "P$6") (pinfunction "GND2_P$6") (pintype "bidirectional"))
      (node (ref "IC4") (pin "P$7") (pinfunction "GND1_P$7") (pintype "bidirectional"))
      (node (ref "IC4") (pin "P$9") (pinfunction "CASE_P$9") (pintype "bidirectional"))
      (node (ref "IC5") (pin "P$4") (pinfunction "EN_P$4") (pintype "bidirectional"))
      (node (ref "IC5") (pin "P$6") (pinfunction "GND2_P$6") (pintype "bidirectional"))
      (node (ref "IC5") (pin "P$7") (pinfunction "GND1_P$7") (pintype "bidirectional"))
      (node (ref "IC5") (pin "P$9") (pinfunction "CASE_P$9") (pintype "bidirectional"))
      (node (ref "IC6") (pin "P$4") (pinfunction "EN_P$4") (pintype "bidirectional"))
      (node (ref "IC6") (pin "P$6") (pinfunction "GND2_P$6") (pintype "bidirectional"))
      (node (ref "IC6") (pin "P$7") (pinfunction "GND1_P$7") (pintype "bidirectional"))
      (node (ref "IC6") (pin "P$9") (pinfunction "CASE_P$9") (pintype "bidirectional"))
      (node (ref "IC7") (pin "P$1") (pinfunction "V_1_P$1") (pintype "bidirectional"))
      (node (ref "IC7") (pin "P$2") (pinfunction "GND_P$2") (pintype "power_in"))
      (node (ref "IC7") (pin "P$4") (pinfunction "V_2_P$4") (pintype "bidirectional"))
      (node (ref "IC7") (pin "P$5") (pinfunction "GND_P$5") (pintype "power_in"))
      (node (ref "IC8") (pin "P$1") (pinfunction "V_1_P$1") (pintype "bidirectional"))
      (node (ref "IC8") (pin "P$2") (pinfunction "GND_P$2") (pintype "power_in"))
      (node (ref "IC8") (pin "P$4") (pinfunction "V_2_P$4") (pintype "bidirectional"))
      (node (ref "IC8") (pin "P$5") (pinfunction "GND_P$5") (pintype "power_in"))
      (node (ref "IC9") (pin "2") (pinfunction "V_1_2") (pintype "bidirectional"))
      (node (ref "IC9") (pin "4") (pinfunction "V_2_4") (pintype "bidirectional"))
      (node (ref "J1") (pin "P1") (pinfunction "GND_P1") (pintype "power_in"))
      (node (ref "J1") (pin "P3") (pinfunction "GND_P3") (pintype "power_in"))
      (node (ref "J1") (pin "P4") (pinfunction "GND_P4") (pintype "power_in"))
      (node (ref "J1") (pin "P5") (pinfunction "GND_P5") (pintype "power_in"))
      (node (ref "J2") (pin "P1") (pinfunction "GND_P1") (pintype "power_in"))
      (node (ref "J2") (pin "P3") (pinfunction "GND_P3") (pintype "power_in"))
      (node (ref "J2") (pin "P4") (pinfunction "GND_P4") (pintype "power_in"))
      (node (ref "J2") (pin "P5") (pinfunction "GND_P5") (pintype "power_in"))
      (node (ref "L12") (pin "1") (pinfunction "1_1") (pintype "passive"))
      (node (ref "L18") (pin "1") (pinfunction "1_1") (pintype "passive"))
      (node (ref "Q2") (pin "2") (pinfunction "E_2") (pintype "passive"))
      (node (ref "R16") (pin "1") (pinfunction "1_1") (pintype "passive"))
      (node (ref "R23") (pin "1") (pinfunction "1_1") (pintype "passive"))
      (node (ref "R36") (pin "1") (pinfunction "1_1") (pintype "passive"))
      (node (ref "R37") (pin "1") (pinfunction "1_1") (pintype "passive"))
      (node (ref "R40") (pin "1") (pinfunction "1_1") (pintype "passive"))
      (node (ref "R43") (pin "2") (pinfunction "2_2") (pintype "passive"))
      (node (ref "R50") (pin "1") (pinfunction "1_1") (pintype "passive"))
      (node (ref "R54") (pin "1") (pinfunction "1_1") (pintype "passive"))
      (node (ref "R58") (pin "1") (pinfunction "1_1") (pintype "passive"))
      (node (ref "R59") (pin "1") (pinfunction "1_1") (pintype "passive"))
      (node (ref "R6") (pin "1") (pinfunction "1_1") (pintype "passive"))
      (node (ref "R62") (pin "1") (pinfunction "1_1") (pintype "passive"))
      (node (ref "R63") (pin "1") (pinfunction "1_1") (pintype "passive"))
      (node (ref "R64") (pin "1") (pinfunction "1_1") (pintype "passive"))
      (node (ref "R7") (pin "1") (pinfunction "1_1") (pintype "passive"))
      (node (ref "S1") (pin "2") (pinfunction "S_2") (pintype "passive"))
      (node (ref "SAW1") (pin "P$1") (pinfunction "GND1_P$1") (pintype "bidirectional"))
      (node (ref "SAW1") (pin "P$3") (pinfunction "GND2_P$3") (pintype "bidirectional"))
      (node (ref "SAW1") (pin "P$4") (pinfunction "GND3_P$4") (pintype "bidirectional"))
      (node (ref "SAW1") (pin "P$6") (pinfunction "GND4_P$6") (pintype "bidirectional"))
      (node (ref "SAW1") (pin "P$7") (pinfunction "GND5_P$7") (pintype "bidirectional"))
      (node (ref "SAW1") (pin "P$8") (pinfunction "GND6_P$8") (pintype "bidirectional"))
      (node (ref "SAW2") (pin "P$1") (pinfunction "GND1_P$1") (pintype "bidirectional"))
      (node (ref "SAW2") (pin "P$3") (pinfunction "GND2_P$3") (pintype "bidirectional"))
      (node (ref "SAW2") (pin "P$4") (pinfunction "GND3_P$4") (pintype "bidirectional"))
      (node (ref "SAW2") (pin "P$6") (pinfunction "GND4_P$6") (pintype "bidirectional"))
      (node (ref "SAW2") (pin "P$7") (pinfunction "GND5_P$7") (pintype "bidirectional"))
      (node (ref "SAW2") (pin "P$8") (pinfunction "GND6_P$8") (pintype "bidirectional"))
      (node (ref "SAW3") (pin "P$1") (pinfunction "GND1_P$1") (pintype "bidirectional"))
      (node (ref "SAW3") (pin "P$3") (pinfunction "GND2_P$3") (pintype "bidirectional"))
      (node (ref "SAW3") (pin "P$4") (pinfunction "GND3_P$4") (pintype "bidirectional"))
      (node (ref "SAW3") (pin "P$6") (pinfunction "GND4_P$6") (pintype "bidirectional"))
      (node (ref "SAW3") (pin "P$7") (pinfunction "GND5_P$7") (pintype "bidirectional"))
      (node (ref "SAW3") (pin "P$8") (pinfunction "GND6_P$8") (pintype "bidirectional"))
      (node (ref "T1") (pin "2") (pinfunction "S_CT_2") (pintype "bidirectional"))
      (node (ref "T1") (pin "4") (pinfunction "P_4") (pintype "bidirectional"))
      (node (ref "TR1") (pin "P4") (pinfunction "P1_P4") (pintype "passive"))
      (node (ref "TR2") (pin "P4") (pinfunction "P1_P4") (pintype "passive"))
      (node (ref "U1") (pin "12") (pinfunction "VSSA_12") (pintype "passive"))
      (node (ref "U1") (pin "18") (pinfunction "VSS_4_18") (pintype "passive"))
      (node (ref "U1") (pin "28") (pinfunction "PB1_2_28") (pintype "bidirectional"))
      (node (ref "U1") (pin "31") (pinfunction "VSS_1_31") (pintype "passive"))
      (node (ref "U1") (pin "47") (pinfunction "VSS_2_47") (pintype "passive"))
      (node (ref "U1") (pin "63") (pinfunction "VSS_3_63") (pintype "passive"))
      (node (ref "U10") (pin "2") (pinfunction "GND_2") (pintype "passive"))
      (node (ref "U11") (pin "2") (pinfunction "GND_2") (pintype "passive"))
      (node (ref "U12") (pin "2") (pinfunction "GND_2") (pintype "passive"))
      (node (ref "U2") (pin "10") (pinfunction "AGND_2_10") (pintype "passive"))
      (node (ref "U2") (pin "12") (pinfunction "AGND_12") (pintype "passive"))
      (node (ref "U2") (pin "16") (pinfunction "AGND_4_16") (pintype "passive"))
      (node (ref "U2") (pin "18") (pinfunction "AGND_5_18") (pintype "passive"))
      (node (ref "U2") (pin "20") (pinfunction "AGND_3_20") (pintype "passive"))
      (node (ref "U2") (pin "25") (pinfunction "AGND_7_25") (pintype "passive"))
      (node (ref "U2") (pin "44") (pinfunction "DGND_2_44") (pintype "passive"))
      (node (ref "U2") (pin "56") (pinfunction "DGND_56") (pintype "passive"))
      (node (ref "U2") (pin "57") (pinfunction "EPAD_57") (pintype "passive"))
      (node (ref "U2") (pin "6") (pinfunction "AGND_6_6") (pintype "passive"))
      (node (ref "U3") (pin "2") (pinfunction "GND_2") (pintype "passive"))
      (node (ref "U4") (pin "2") (pinfunction "GND_2") (pintype "passive"))
      (node (ref "U5") (pin "1") (pinfunction "COMM_1") (pintype "passive"))
      (node (ref "U5") (pin "10") (pinfunction "ACOM_2_10") (pintype "passive"))
      (node (ref "U5") (pin "16") (pinfunction "ACOM_16") (pintype "passive"))
      (node (ref "U5") (pin "7") (pinfunction "PWDN_7") (pintype "input"))
      (node (ref "U5") (pin "8") (pinfunction "COMM_2_8") (pintype "passive"))
      (node (ref "U6") (pin "2") (pinfunction "GND_2") (pintype "passive"))
      (node (ref "U7") (pin "2") (pinfunction "GND_2") (pintype "passive"))
      (node (ref "U8") (pin "1") (pinfunction "COMM_2_1") (pintype "passive"))
      (node (ref "U8") (pin "7") (pinfunction "COMM_7") (pintype "passive"))
      (node (ref "U9") (pin "2") (pinfunction "GND_2") (pintype "passive"))
      (node (ref "X1") (pin "5") (pinfunction "5_5") (pintype "input"))
      (node (ref "X1") (pin "M1") (pinfunction "GND1_M1") (pintype "bidirectional"))
      (node (ref "X1") (pin "M2") (pinfunction "GND2_M2") (pintype "bidirectional"))
      (node (ref "X1") (pin "M3") (pinfunction "GND3_M3") (pintype "bidirectional"))
      (node (ref "X1") (pin "M4") (pinfunction "GND4_M4") (pintype "bidirectional"))
      (node (ref "X2") (pin "5") (pinfunction "5_5") (pintype "input"))
      (node (ref "X2") (pin "M1") (pinfunction "GND1_M1") (pintype "bidirectional"))
      (node (ref "X2") (pin "M2") (pinfunction "GND2_M2") (pintype "bidirectional"))
      (node (ref "X2") (pin "M3") (pinfunction "GND3_M3") (pintype "bidirectional"))
      (node (ref "X2") (pin "M4") (pinfunction "GND4_M4") (pintype "bidirectional"))
      (node (ref "X3") (pin "2") (pinfunction "2_2") (pintype "passive"))
      (node (ref "X3") (pin "3") (pinfunction "3_3") (pintype "passive"))
    )
    (net (code "15") (name "INA_8302") (class "Default")
      (node (ref "C53") (pin "1") (pinfunction "1_1") (pintype "passive"))
      (node (ref "R36") (pin "2") (pinfunction "2_2") (pintype "passive"))
      (node (ref "R44") (pin "2") (pinfunction "2_2") (pintype "passive"))
    )
    (net (code "16") (name "INB_8302") (class "Default")
      (node (ref "C107") (pin "2") (pinfunction "2_2") (pintype "passive"))
      (node (ref "C56") (pin "1") (pinfunction "1_1") (pintype "passive"))
      (node (ref "R37") (pin "2") (pinfunction "2_2") (pintype "passive"))
    )
    (net (code "17") (name "IN_8362") (class "Default")
      (node (ref "C37") (pin "1") (pinfunction "1_1") (pintype "passive"))
      (node (ref "R46") (pin "1") (pinfunction "1_1") (pintype "passive"))
    )
    (net (code "18") (name "IO_UP_DDS") (class "Default")
      (node (ref "U1") (pin "49") (pinfunction "PA14_49") (pintype "bidirectional"))
      (node (ref "U2") (pin "46") (pinfunction "I/O_UPDATE_46") (pintype "bidirectional"))
    )
    (net (code "19") (name "MAG") (class "Default")
      (node (ref "R21") (pin "2") (pinfunction "2_2") (pintype "passive"))
      (node (ref "R35") (pin "2") (pinfunction "2_2") (pintype "passive"))
      (node (ref "U1") (pin "26") (pinfunction "PB0_26") (pintype "bidirectional"))
    )
    (net (code "20") (name "Net-(C30-Pad2)") (class "Default")
      (node (ref "C30") (pin "2") (pinfunction "2_2") (pintype "passive"))
      (node (ref "R19") (pin "1") (pinfunction "1_1") (pintype "passive"))
    )
    (net (code "21") (name "Net-(C60-Pad1)") (class "Default")
      (node (ref "C60") (pin "1") (pinfunction "1_1") (pintype "passive"))
      (node (ref "C61") (pin "1") (pinfunction "1_1") (pintype "passive"))
      (node (ref "C62") (pin "1") (pinfunction "1_1") (pintype "passive"))
      (node (ref "L5") (pin "2") (pinfunction "2_2") (pintype "passive"))
      (node (ref "R38") (pin "1") (pinfunction "1_1") (pintype "passive"))
    )
    (net (code "22") (name "Net-(C63-Pad1)") (class "Default")
      (node (ref "C63") (pin "1") (pinfunction "1_1") (pintype "passive"))
      (node (ref "C64") (pin "1") (pinfunction "1_1") (pintype "passive"))
      (node (ref "C65") (pin "1") (pinfunction "1_1") (pintype "passive"))
      (node (ref "L6") (pin "2") (pinfunction "2_2") (pintype "passive"))
      (node (ref "R39") (pin "1") (pinfunction "1_1") (pintype "passive"))
    )
    (net (code "23") (name "Net-(C72-Pad2)") (class "Default")
      (node (ref "C72") (pin "2") (pinfunction "2_2") (pintype "passive"))
      (node (ref "R40") (pin "2") (pinfunction "2_2") (pintype "passive"))
    )
    (net (code "24") (name "Net-(C74-Pad2)") (class "Default")
      (node (ref "C74") (pin "2") (pinfunction "2_2") (pintype "passive"))
      (node (ref "C75") (pin "1") (pinfunction "1_1") (pintype "passive"))
      (node (ref "L9") (pin "1") (pinfunction "1_1") (pintype "passive"))
    )
    (net (code "25") (name "Net-(C76-Pad1)") (class "Default")
      (node (ref "C76") (pin "1") (pinfunction "1_1") (pintype "passive"))
      (node (ref "L10") (pin "1") (pinfunction "1_1") (pintype "passive"))
      (node (ref "L9") (pin "2") (pinfunction "2_2") (pintype "passive"))
    )
    (net (code "26") (name "Net-(C76-Pad2)") (class "Default")
      (node (ref "C76") (pin "2") (pinfunction "2_2") (pintype "passive"))
      (node (ref "L12") (pin "2") (pinfunction "2_2") (pintype "passive"))
    )
    (net (code "27") (name "Net-(C80-Pad1)") (class "Default")
      (node (ref "C80") (pin "1") (pinfunction "1_1") (pintype "passive"))
      (node (ref "C81") (pin "1") (pinfunction "1_1") (pintype "passive"))
      (node (ref "C82") (pin "1") (pinfunction "1_1") (pintype "passive"))
      (node (ref "L14") (pin "2") (pinfunction "2_2") (pintype "passive"))
      (node (ref "R41") (pin "1") (pinfunction "1_1") (pintype "passive"))
    )
    (net (code "28") (name "Net-(C83-Pad1)") (class "Default")
      (node (ref "C83") (pin "1") (pinfunction "1_1") (pintype "passive"))
      (node (ref "C84") (pin "1") (pinfunction "1_1") (pintype "passive"))
      (node (ref "C85") (pin "1") (pinfunction "1_1") (pintype "passive"))
      (node (ref "L15") (pin "2") (pinfunction "2_2") (pintype "passive"))
      (node (ref "R42") (pin "1") (pinfunction "1_1") (pintype "passive"))
    )
    (net (code "29") (name "Net-(C87-Pad1)") (class "Default")
      (node (ref "C87") (pin "1") (pinfunction "1_1") (pintype "passive"))
      (node (ref "R43") (pin "1") (pinfunction "1_1") (pintype "passive"))
    )
    (net (code "30") (name "Net-(C92-Pad2)") (class "Default")
      (node (ref "C92") (pin "2") (pinfunction "2_2") (pintype "passive"))
      (node (ref "C95") (pin "1") (pinfunction "1_1") (pintype "passive"))
      (node (ref "L17") (pin "1") (pinfunction "1_1") (pintype "passive"))
    )
    (net (code "31") (name "Net-(C93-Pad1)") (class "Default")
      (node (ref "C93") (pin "1") (pinfunction "1_1") (pintype "passive"))
      (node (ref "L16") (pin "2") (pinfunction "2_2") (pintype "passive"))
      (node (ref "R45") (pin "2") (pinfunction "2_2") (pintype "passive"))
    )
    (net (code "32") (name "Net-(C94-Pad1)") (class "Default")
      (node (ref "C94") (pin "1") (pinfunction "1_1") (pintype "passive"))
      (node (ref "L16") (pin "1") (pinfunction "1_1") (pintype "passive"))
      (node (ref "L17") (pin "2") (pinfunction "2_2") (pintype "passive"))
    )
    (net (code "33") (name "Net-(C94-Pad2)") (class "Default")
      (node (ref "C94") (pin "2") (pinfunction "2_2") (pintype "passive"))
      (node (ref "L18") (pin "2") (pinfunction "2_2") (pintype "passive"))
    )
    (net (code "34") (name "Net-(C100-Pad1)") (class "Default")
      (node (ref "C100") (pin "1") (pinfunction "1_1") (pintype "passive"))
      (node (ref "C98") (pin "1") (pinfunction "1_1") (pintype "passive"))
      (node (ref "C99") (pin "1") (pinfunction "1_1") (pintype "passive"))
      (node (ref "L19") (pin "2") (pinfunction "2_2") (pintype "passive"))
      (node (ref "R47") (pin "1") (pinfunction "1_1") (pintype "passive"))
    )
    (net (code "35") (name "Net-(C101-Pad1)") (class "Default")
      (node (ref "C101") (pin "1") (pinfunction "1_1") (pintype "passive"))
      (node (ref "C102") (pin "1") (pinfunction "1_1") (pintype "passive"))
      (node (ref "C103") (pin "1") (pinfunction "1_1") (pintype "passive"))
      (node (ref "L20") (pin "2") (pinfunction "2_2") (pintype "passive"))
      (node (ref "R48") (pin "1") (pinfunction "1_1") (pintype "passive"))
    )
    (net (code "36") (name "Net-(D1-PadA1)") (class "Default")
      (node (ref "D1") (pin "A1") (pinfunction "A1_A1") (pintype "passive"))
      (node (ref "R10") (pin "1") (pinfunction "1_1") (pintype "passive"))
    )
    (net (code "37") (name "Net-(D1-PadA2)") (class "Default")
      (node (ref "D1") (pin "A2") (pinfunction "A2_A2") (pintype "passive"))
      (node (ref "R8") (pin "1") (pinfunction "1_1") (pintype "passive"))
    )
    (net (code "38") (name "Net-(DZ1A-C)") (class "Default")
      (node (ref "DZ1") (pin "K1") (pinfunction "C_K1") (pintype "passive"))
      (node (ref "R62") (pin "2") (pinfunction "2_2") (pintype "passive"))
    )
    (net (code "39") (name "Net-(DZ1B-C)") (class "Default")
      (node (ref "DZ1") (pin "K2") (pinfunction "C_K2") (pintype "passive"))
      (node (ref "R63") (pin "2") (pinfunction "2_2") (pintype "passive"))
    )
    (net (code "40") (name "Net-(D_MAG-P)") (class "Default")
      (node (ref "D_MAG") (pin "1") (pinfunction "P_1") (pintype "passive"))
      (node (ref "R31") (pin "1") (pinfunction "1_1") (pintype "passive"))
      (node (ref "R33") (pin "1") (pinfunction "1_1") (pintype "passive"))
      (node (ref "U8") (pin "13") (pinfunction "VMAG_13") (pintype "output"))
    )
    (net (code "41") (name "Net-(D_P-P)") (class "Default")
      (node (ref "D_P") (pin "1") (pinfunction "P_1") (pintype "passive"))
      (node (ref "R22") (pin "1") (pinfunction "1_1") (pintype "passive"))
      (node (ref "U5") (pin "11") (pinfunction "VSET_11") (pintype "input"))
      (node (ref "U5") (pin "12") (pinfunction "VOUT_12") (pintype "output"))
    )
    (net (code "42") (name "Net-(D_PH-P)") (class "Default")
      (node (ref "D_PH") (pin "1") (pinfunction "P_1") (pintype "passive"))
      (node (ref "R30") (pin "1") (pinfunction "1_1") (pintype "passive"))
      (node (ref "U8") (pin "10") (pinfunction "PSET_10") (pintype "input"))
      (node (ref "U8") (pin "9") (pinfunction "VPHS_9") (pintype "output"))
    )
    (net (code "43") (name "Net-(F1A-IN)") (class "Default")
      (node (ref "C67") (pin "2") (pinfunction "2_2") (pintype "passive"))
      (node (ref "F1") (pin "P$2") (pinfunction "IN_P$2") (pintype "bidirectional"))
      (node (ref "SAW1") (pin "P$2") (pinfunction "1_P$2") (pintype "bidirectional"))
    )
    (net (code "44") (name "Net-(F1A-OUT)") (class "Default")
      (node (ref "C68") (pin "1") (pinfunction "1_1") (pintype "passive"))
      (node (ref "F1") (pin "P$5") (pinfunction "OUT_P$5") (pintype "bidirectional"))
      (node (ref "SAW1") (pin "P$5") (pinfunction "2_P$5") (pintype "bidirectional"))
    )
    (net (code "45") (name "Net-(F2A-IN)") (class "Default")
      (node (ref "C91") (pin "2") (pinfunction "2_2") (pintype "passive"))
      (node (ref "F2") (pin "P$2") (pinfunction "IN_P$2") (pintype "bidirectional"))
      (node (ref "SAW2") (pin "P$2") (pinfunction "1_P$2") (pintype "bidirectional"))
    )
    (net (code "46") (name "Net-(F2A-OUT)") (class "Default")
      (node (ref "C90") (pin "1") (pinfunction "1_1") (pintype "passive"))
      (node (ref "F2") (pin "P$5") (pinfunction "OUT_P$5") (pintype "bidirectional"))
      (node (ref "SAW2") (pin "P$5") (pinfunction "2_P$5") (pintype "bidirectional"))
    )
    (net (code "47") (name "Net-(F3A-IN)") (class "Default")
      (node (ref "C104") (pin "2") (pinfunction "2_2") (pintype "passive"))
      (node (ref "F3") (pin "P$2") (pinfunction "IN_P$2") (pintype "bidirectional"))
      (node (ref "SAW3") (pin "P$2") (pinfunction "1_P$2") (pintype "bidirectional"))
    )
    (net (code "48") (name "Net-(F3A-OUT)") (class "Default")
      (node (ref "C105") (pin "1") (pinfunction "1_1") (pintype "passive"))
      (node (ref "F3") (pin "P$5") (pinfunction "OUT_P$5") (pintype "bidirectional"))
      (node (ref "SAW3") (pin "P$5") (pinfunction "2_P$5") (pintype "bidirectional"))
    )
    (net (code "49") (name "Net-(IC1-3V3OUT)") (class "Default")
      (node (ref "C9") (pin "1") (pinfunction "1_1") (pintype "passive"))
      (node (ref "IC1") (pin "17") (pinfunction "3V3OUT_17") (pintype "output"))
    )
    (net (code "50") (name "Net-(IC1-RXD)") (class "Default")
      (node (ref "IC1") (pin "5") (pinfunction "RXD_5") (pintype "input"))
      (node (ref "R3") (pin "1") (pinfunction "1_1") (pintype "passive"))
    )
    (net (code "51") (name "Net-(IC1-TXD)") (class "Default")
      (node (ref "IC1") (pin "1") (pinfunction "TXD_1") (pintype "output"))
      (node (ref "R1") (pin "1") (pinfunction "1_1") (pintype "passive"))
    )
    (net (code "52") (name "Net-(IC1-USBDM)") (class "Default")
      (node (ref "IC1") (pin "16") (pinfunction "USBDM_16") (pintype "bidirectional"))
      (node (ref "X1") (pin "2") (pinfunction "2_2") (pintype "input"))
    )
    (net (code "53") (name "Net-(IC1-USBDP)") (class "Default")
      (node (ref "IC1") (pin "15") (pinfunction "USBDP_15") (pintype "bidirectional"))
      (node (ref "X1") (pin "3") (pinfunction "3_3") (pintype "input"))
    )
    (net (code "54") (name "Net-(IC1-VCC)") (class "Default")
      (node (ref "IC1") (pin "20") (pinfunction "VCC_20") (pintype "power_in"))
      (node (ref "R2") (pin "2") (pinfunction "2_2") (pintype "passive"))
      (node (ref "R55") (pin "2") (pinfunction "2_2") (pintype "passive"))
      (node (ref "X1") (pin "1") (pinfunction "1_1") (pintype "input"))
    )
    (net (code "55") (name "Net-(IC2-IN)") (class "Default")
      (node (ref "C68") (pin "2") (pinfunction "2_2") (pintype "passive"))
      (node (ref "IC2") (pin "1") (pinfunction "IN_1") (pintype "bidirectional"))
    )
    (net (code "56") (name "Net-(IC2-OUT)") (class "Default")
      (node (ref "C69") (pin "1") (pinfunction "1_1") (pintype "passive"))
      (node (ref "IC2") (pin "3") (pinfunction "OUT_3") (pintype "bidirectional"))
      (node (ref "L5") (pin "1") (pinfunction "1_1") (pintype "passive"))
    )
    (net (code "57") (name "Net-(IC3-IN)") (class "Default")
      (node (ref "C69") (pin "2") (pinfunction "2_2") (pintype "passive"))
      (node (ref "IC3") (pin "1") (pinfunction "IN_1") (pintype "bidirectional"))
    )
    (net (code "58") (name "Net-(IC3-OUT)") (class "Default")
      (node (ref "C70") (pin "1") (pinfunction "1_1") (pintype "passive"))
      (node (ref "IC3") (pin "3") (pinfunction "OUT_3") (pintype "bidirectional"))
      (node (ref "L6") (pin "1") (pinfunction "1_1") (pintype "passive"))
    )
    (net (code "59") (name "Net-(IC4-CTL)") (class "Default")
      (node (ref "IC4") (pin "P$2") (pinfunction "CTL_P$2") (pintype "bidirectional"))
      (node (ref "L4") (pin "1") (pinfunction "1_1") (pintype "passive"))
    )
    (net (code "60") (name "Net-(IC4-RF1)") (class "Default")
      (node (ref "C72") (pin "1") (pinfunction "1_1") (pintype "passive"))
      (node (ref "IC4") (pin "P$5") (pinfunction "RF1_P$5") (pintype "bidirectional"))
    )
    (net (code "61") (name "Net-(IC4-RF2)") (class "Default")
      (node (ref "C67") (pin "1") (pinfunction "1_1") (pintype "passive"))
      (node (ref "IC4") (pin "P$8") (pinfunction "RF2_P$8") (pintype "bidirectional"))
    )
    (net (code "62") (name "Net-(IC4-RFC)") (class "Default")
      (node (ref "C71") (pin "2") (pinfunction "2_2") (pintype "passive"))
      (node (ref "IC4") (pin "P$3") (pinfunction "RFC_P$3") (pintype "bidirectional"))
    )
    (net (code "63") (name "Net-(IC4-VDD)") (class "Default")
      (node (ref "C66") (pin "1") (pinfunction "1_1") (pintype "passive"))
      (node (ref "IC4") (pin "P$1") (pinfunction "VDD_P$1") (pintype "bidirectional"))
      (node (ref "L3") (pin "1") (pinfunction "1_1") (pintype "passive"))
    )
    (net (code "64") (name "Net-(IC5-CTL)") (class "Default")
      (node (ref "IC5") (pin "P$2") (pinfunction "CTL_P$2") (pintype "bidirectional"))
      (node (ref "L8") (pin "1") (pinfunction "1_1") (pintype "passive"))
    )
    (net (code "65") (name "Net-(IC5-RF1)") (class "Default")
      (node (ref "C91") (pin "1") (pinfunction "1_1") (pintype "passive"))
      (node (ref "IC5") (pin "P$5") (pinfunction "RF1_P$5") (pintype "bidirectional"))
    )
    (net (code "66") (name "Net-(IC5-RF2)") (class "Default")
      (node (ref "C70") (pin "2") (pinfunction "2_2") (pintype "passive"))
      (node (ref "IC5") (pin "P$8") (pinfunction "RF2_P$8") (pintype "bidirectional"))
    )
    (net (code "67") (name "Net-(IC5-RFC)") (class "Default")
      (node (ref "C74") (pin "1") (pinfunction "1_1") (pintype "passive"))
      (node (ref "IC5") (pin "P$3") (pinfunction "RFC_P$3") (pintype "bidirectional"))
    )
    (net (code "68") (name "Net-(IC5-VDD)") (class "Default")
      (node (ref "C73") (pin "1") (pinfunction "1_1") (pintype "passive"))
      (node (ref "IC5") (pin "P$1") (pinfunction "VDD_P$1") (pintype "bidirectional"))
      (node (ref "L7") (pin "1") (pinfunction "1_1") (pintype "passive"))
    )
    (net (code "69") (name "Net-(IC6-CTL)") (class "Default")
      (node (ref "IC6") (pin "P$2") (pinfunction "CTL_P$2") (pintype "bidirectional"))
      (node (ref "L13") (pin "1") (pinfunction "1_1") (pintype "passive"))
    )
    (net (code "70") (name "Net-(IC6-RF1)") (class "Default")
      (node (ref "C92") (pin "1") (pinfunction "1_1") (pintype "passive"))
      (node (ref "IC6") (pin "P$5") (pinfunction "RF1_P$5") (pintype "bidirectional"))
    )
    (net (code "71") (name "Net-(IC6-RF2)") (class "Default")
      (node (ref "C87") (pin "2") (pinfunction "2_2") (pintype "passive"))
      (node (ref "IC6") (pin "P$8") (pinfunction "RF2_P$8") (pintype "bidirectional"))
    )
    (net (code "72") (name "Net-(IC6-RFC)") (class "Default")
      (node (ref "C88") (pin "2") (pinfunction "2_2") (pintype "passive"))
      (node (ref "IC6") (pin "P$3") (pinfunction "RFC_P$3") (pintype "bidirectional"))
    )
    (net (code "73") (name "Net-(IC6-VDD)") (class "Default")
      (node (ref "C86") (pin "1") (pinfunction "1_1") (pintype "passive"))
      (node (ref "IC6") (pin "P$1") (pinfunction "VDD_P$1") (pintype "bidirectional"))
      (node (ref "L11") (pin "1") (pinfunction "1_1") (pintype "passive"))
    )
    (net (code "74") (name "Net-(IC7A-IN)") (class "Default")
      (node (ref "C89") (pin "2") (pinfunction "2_2") (pintype "passive"))
      (node (ref "IC7") (pin "P$3") (pinfunction "IN_P$3") (pintype "bidirectional"))
    )
    (net (code "75") (name "Net-(IC7A-OUT)") (class "Default")
      (node (ref "C88") (pin "1") (pinfunction "1_1") (pintype "passive"))
      (node (ref "IC7") (pin "P$6") (pinfunction "OUT_P$6") (pintype "bidirectional"))
      (node (ref "L14") (pin "1") (pinfunction "1_1") (pintype "passive"))
    )
    (net (code "76") (name "Net-(IC8A-IN)") (class "Default")
      (node (ref "C90") (pin "2") (pinfunction "2_2") (pintype "passive"))
      (node (ref "IC8") (pin "P$3") (pinfunction "IN_P$3") (pintype "bidirectional"))
    )
    (net (code "77") (name "Net-(IC8A-OUT)") (class "Default")
      (node (ref "C89") (pin "1") (pinfunction "1_1") (pintype "passive"))
      (node (ref "IC8") (pin "P$6") (pinfunction "OUT_P$6") (pintype "bidirectional"))
      (node (ref "L15") (pin "1") (pinfunction "1_1") (pintype "passive"))
    )
    (net (code "78") (name "Net-(IC9-IN)") (class "Default")
      (node (ref "C105") (pin "2") (pinfunction "2_2") (pintype "passive"))
      (node (ref "IC9") (pin "1") (pinfunction "IN_1") (pintype "bidirectional"))
    )
    (net (code "79") (name "Net-(IC9-OUT)") (class "Default")
      (node (ref "C106") (pin "1") (pinfunction "1_1") (pintype "passive"))
      (node (ref "IC9") (pin "3") (pinfunction "OUT_3") (pintype "bidirectional"))
      (node (ref "L19") (pin "1") (pinfunction "1_1") (pintype "passive"))
    )
    (net (code "80") (name "Net-(IC10-IN)") (class "Default")
      (node (ref "C106") (pin "2") (pinfunction "2_2") (pintype "passive"))
      (node (ref "IC10") (pin "1") (pinfunction "IN_1") (pintype "bidirectional"))
    )
    (net (code "81") (name "Net-(IC10-OUT)") (class "Default")
      (node (ref "C107") (pin "1") (pinfunction "1_1") (pintype "passive"))
      (node (ref "IC10") (pin "3") (pinfunction "OUT_3") (pintype "bidirectional"))
      (node (ref "L20") (pin "1") (pinfunction "1_1") (pintype "passive"))
    )
    (net (code "82") (name "Net-(J1A-1)") (class "Default")
      (node (ref "J1") (pin "P2") (pinfunction "1_P2") (pintype "passive"))
      (node (ref "U3") (pin "1") (pinfunction "OUT_1") (pintype "output"))
      (node (ref "U3") (pin "4") (pinfunction "IN-_4") (pintype "input"))
    )
    (net (code "83") (name "Net-(J2A-1)") (class "Default")
      (node (ref "C77") (pin "1") (pinfunction "1_1") (pintype "passive"))
      (node (ref "D8") (pin "C") (pinfunction "C_C") (pintype "passive"))
      (node (ref "J2") (pin "P2") (pinfunction "1_P2") (pintype "passive"))
      (node (ref "L10") (pin "2") (pinfunction "2_2") (pintype "passive"))
    )
    (net (code "84") (name "Net-(JP1-Pad1)") (class "Default")
      (node (ref "JP1") (pin "1") (pinfunction "1_1") (pintype "passive"))
      (node (ref "R5") (pin "2") (pinfunction "2_2") (pintype "passive"))
    )
    (net (code "85") (name "Net-(L21COILCRAFT_LPS6225-103-1)") (class "Default")
      (node (ref "C117") (pin "1") (pinfunction "1_1") (pintype "passive"))
      (node (ref "D2") (pin "C") (pinfunction "C_C") (pintype "passive"))
      (node (ref "D5") (pin "C") (pinfunction "C_C") (pintype "passive"))
      (node (ref "L21COILCRAFT_LPS6225-103") (pin "P$1") (pinfunction "1_P$1") (pintype "passive"))
      (node (ref "U10") (pin "6") (pinfunction "SW_6") (pintype "output"))
    )
    (net (code "86") (name "Net-(L22COILCRAFT_LPS6225-103-1)") (class "Default")
      (node (ref "C113") (pin "1") (pinfunction "1_1") (pintype "passive"))
      (node (ref "D3") (pin "C") (pinfunction "C_C") (pintype "passive"))
      (node (ref "D4") (pin "C") (pinfunction "C_C") (pintype "passive"))
      (node (ref "L22COILCRAFT_LPS6225-103") (pin "P$1") (pinfunction "1_P$1") (pintype "passive"))
      (node (ref "U11") (pin "6") (pinfunction "SW_6") (pintype "output"))
    )
    (net (code "87") (name "Net-(L23COILCRAFT_LPS6225-103-1)") (class "Default")
      (node (ref "C119") (pin "1") (pinfunction "1_1") (pintype "passive"))
      (node (ref "D6") (pin "C") (pinfunction "C_C") (pintype "passive"))
      (node (ref "D7") (pin "C") (pinfunction "C_C") (pintype "passive"))
      (node (ref "L23COILCRAFT_LPS6225-103") (pin "P$1") (pinfunction "1_P$1") (pintype "passive"))
      (node (ref "U12") (pin "6") (pinfunction "SW_6") (pintype "output"))
    )
    (net (code "88") (name "Net-(Q1-1)") (class "Default")
      (node (ref "C8") (pin "1") (pinfunction "1_1") (pintype "passive"))
      (node (ref "Q1") (pin "P$1") (pinfunction "1_P$1") (pintype "passive"))
      (node (ref "U1") (pin "5") (pinfunction "PD0_OSC_IN_5") (pintype "input"))
    )
    (net (code "89") (name "Net-(Q1-2)") (class "Default")
      (node (ref "C7") (pin "1") (pinfunction "1_1") (pintype "passive"))
      (node (ref "Q1") (pin "P$3") (pinfunction "2_P$3") (pintype "passive"))
      (node (ref "U1") (pin "6") (pinfunction "PD1_OSC_OUT_6") (pintype "output"))
    )
    (net (code "90") (name "Net-(Q3-1)") (class "Default")
      (node (ref "C11") (pin "1") (pinfunction "1_1") (pintype "passive"))
      (node (ref "Q3") (pin "P$1") (pinfunction "1_P$1") (pintype "passive"))
      (node (ref "U1") (pin "2") (pinfunction "PC13-TAMPER-RTC_2") (pintype "input"))
    )
    (net (code "91") (name "Net-(Q3-2)") (class "Default")
      (node (ref "C10") (pin "1") (pinfunction "1_1") (pintype "passive"))
      (node (ref "Q3") (pin "P$2") (pinfunction "2_P$2") (pintype "passive"))
      (node (ref "U1") (pin "3") (pinfunction "PC14-OSC32_IN_3") (pintype "input"))
    )
    (net (code "92") (name "Net-(Q4-1)") (class "Default")
      (node (ref "C28") (pin "1") (pinfunction "1_1") (pintype "passive"))
      (node (ref "Q4") (pin "P$1") (pinfunction "1_P$1") (pintype "passive"))
      (node (ref "U2") (pin "22") (pinfunction "~{REF_CLK}_22") (pintype "input"))
    )
    (net (code "93") (name "Net-(Q4-2)") (class "Default")
      (node (ref "C29") (pin "1") (pinfunction "1_1") (pintype "passive"))
      (node (ref "Q4") (pin "P$3") (pinfunction "2_P$3") (pintype "passive"))
      (node (ref "U2") (pin "23") (pinfunction "REF_CLK_23") (pintype "input"))
    )
    (net (code "94") (name "Net-(R11-Pad1)") (class "Default")
      (node (ref "R11") (pin "1") (pinfunction "1_1") (pintype "passive"))
      (node (ref "X2") (pin "2") (pinfunction "2_2") (pintype "input"))
    )
    (net (code "95") (name "Net-(R12-Pad1)") (class "Default")
      (node (ref "R12") (pin "1") (pinfunction "1_1") (pintype "passive"))
      (node (ref "R9") (pin "1") (pinfunction "1_1") (pintype "passive"))
      (node (ref "X2") (pin "3") (pinfunction "3_3") (pintype "input"))
    )
    (net (code "96") (name "Net-(R44-Pad1)") (class "Default")
      (node (ref "R44") (pin "1") (pinfunction "1_1") (pintype "passive"))
      (node (ref "R45") (pin "1") (pinfunction "1_1") (pintype "passive"))
      (node (ref "R46") (pin "2") (pinfunction "2_2") (pintype "passive"))
    )
    (net (code "97") (name "Net-(R60-Pad2)") (class "Default")
      (node (ref "R60") (pin "2") (pinfunction "2_2") (pintype "passive"))
      (node (ref "R9") (pin "2") (pinfunction "2_2") (pintype "passive"))
      (node (ref "X2") (pin "1") (pinfunction "1_1") (pintype "input"))
    )
    (net (code "98") (name "Net-(T1-P_DT)") (class "Default")
      (node (ref "C37") (pin "2") (pinfunction "2_2") (pintype "passive"))
      (node (ref "T1") (pin "5") (pinfunction "P_DT_5") (pintype "bidirectional"))
    )
    (net (code "99") (name "Net-(T1-S)") (class "Default")
      (node (ref "C38") (pin "1") (pinfunction "1_1") (pintype "passive"))
      (node (ref "T1") (pin "3") (pinfunction "S_3") (pintype "bidirectional"))
    )
    (net (code "100") (name "Net-(T1-S_DT)") (class "Default")
      (node (ref "C39") (pin "1") (pinfunction "1_1") (pintype "passive"))
      (node (ref "T1") (pin "1") (pinfunction "S_DT_1") (pintype "bidirectional"))
    )
    (net (code "101") (name "Net-(TR1-S1)") (class "Default")
      (node (ref "R13") (pin "1") (pinfunction "1_1") (pintype "passive"))
      (node (ref "TR1") (pin "P3") (pinfunction "S1_P3") (pintype "passive"))
      (node (ref "U2") (pin "8") (pinfunction "CH0_IOUT_8") (pintype "output"))
    )
    (net (code "102") (name "Net-(TR1-S3)") (class "Default")
      (node (ref "R14") (pin "1") (pinfunction "1_1") (pintype "passive"))
      (node (ref "TR1") (pin "P1") (pinfunction "S3_P1") (pintype "passive"))
      (node (ref "U2") (pin "9") (pinfunction "~{CH0_IOUT}_9") (pintype "output"))
    )
    (net (code "103") (name "Net-(TR2-S1)") (class "Default")
      (node (ref "R17") (pin "1") (pinfunction "1_1") (pintype "passive"))
      (node (ref "TR2") (pin "P3") (pinfunction "S1_P3") (pintype "passive"))
      (node (ref "U2") (pin "13") (pinfunction "CH1_IOUT_13") (pintype "output"))
    )
    (net (code "104") (name "Net-(TR2-S3)") (class "Default")
      (node (ref "R18") (pin "1") (pinfunction "1_1") (pintype "passive"))
      (node (ref "TR2") (pin "P1") (pinfunction "S3_P1") (pintype "passive"))
      (node (ref "U2") (pin "14") (pinfunction "~{CH1_IOUT}_14") (pintype "output"))
    )
    (net (code "105") (name "Net-(U1-PA11)") (class "Default")
      (node (ref "R11") (pin "2") (pinfunction "2_2") (pintype "passive"))
      (node (ref "U1") (pin "44") (pinfunction "PA11_44") (pintype "bidirectional"))
    )
    (net (code "106") (name "Net-(U1-PA12)") (class "Default")
      (node (ref "R12") (pin "2") (pinfunction "2_2") (pintype "passive"))
      (node (ref "U1") (pin "45") (pinfunction "PA12_45") (pintype "bidirectional"))
    )
    (net (code "107") (name "Net-(U1-PB6)") (class "Default")
      (node (ref "R61") (pin "2") (pinfunction "2_2") (pintype "passive"))
      (node (ref "U1") (pin "58") (pinfunction "PB6_58") (pintype "bidirectional"))
    )
    (net (code "108") (name "Net-(U2-AVDD)") (class "Default")
      (node (ref "C12") (pin "1") (pinfunction "1_1") (pintype "passive"))
      (node (ref "C13") (pin "1") (pinfunction "1_1") (pintype "passive"))
      (node (ref "C14") (pin "1") (pinfunction "1_1") (pintype "passive"))
      (node (ref "C15") (pin "1") (pinfunction "1_1") (pintype "passive"))
      (node (ref "C16") (pin "1") (pinfunction "1_1") (pintype "passive"))
      (node (ref "C17") (pin "1") (pinfunction "1_1") (pintype "passive"))
      (node (ref "C18") (pin "1") (pinfunction "1_1") (pintype "passive"))
      (node (ref "C19") (pin "1") (pinfunction "1_1") (pintype "passive"))
      (node (ref "C20") (pin "1") (pinfunction "1_1") (pintype "passive"))
      (node (ref "C21") (pin "1") (pinfunction "1_1") (pintype "passive"))
      (node (ref "C22") (pin "1") (pinfunction "1_1") (pintype "passive"))
      (node (ref "L2") (pin "1") (pinfunction "1_1") (pintype "passive"))
      (node (ref "U2") (pin "11") (pinfunction "AVDD_5_11") (pintype "power_in"))
      (node (ref "U2") (pin "15") (pinfunction "AVDD_9_15") (pintype "power_in"))
      (node (ref "U2") (pin "19") (pinfunction "AVDD_14_19") (pintype "power_in"))
      (node (ref "U2") (pin "21") (pinfunction "AVDD_21") (pintype "power_in"))
      (node (ref "U2") (pin "26") (pinfunction "AVDD_7_26") (pintype "power_in"))
      (node (ref "U2") (pin "29") (pinfunction "AVDD_3_29") (pintype "power_in"))
      (node (ref "U2") (pin "30") (pinfunction "AVDD_4_30") (pintype "power_in"))
      (node (ref "U2") (pin "31") (pinfunction "AVDD_8_31") (pintype "power_in"))
      (node (ref "U2") (pin "33") (pinfunction "AVDD_6_33") (pintype "power_in"))
      (node (ref "U2") (pin "35") (pinfunction "AVDD_12_35") (pintype "power_in"))
      (node (ref "U2") (pin "36") (pinfunction "AVDD_13_36") (pintype "power_in"))
      (node (ref "U2") (pin "37") (pinfunction "AVDD_10_37") (pintype "power_in"))
      (node (ref "U2") (pin "39") (pinfunction "AVDD_15_39") (pintype "power_in"))
      (node (ref "U2") (pin "5") (pinfunction "AVDD_11_5") (pintype "power_in"))
      (node (ref "U2") (pin "7") (pinfunction "AVDD_2_7") (pintype "power_in"))
    )
    (net (code "109") (name "Net-(U2-CLK_MODE_SEL)") (class "Default")
      (node (ref "R15") (pin "2") (pinfunction "2_2") (pintype "passive"))
      (node (ref "U2") (pin "24") (pinfunction "CLK_MODE_SEL_24") (pintype "input"))
    )
    (net (code "110") (name "Net-(U2-DAC_RSET)") (class "Default")
      (node (ref "R16") (pin "2") (pinfunction "2_2") (pintype "passive"))
      (node (ref "U2") (pin "17") (pinfunction "DAC_RSET_17") (pintype "input"))
    )
    (net (code "111") (name "Net-(U2-DVDD)") (class "Default")
      (node (ref "C24") (pin "1") (pinfunction "1_1") (pintype "passive"))
      (node (ref "C25") (pin "1") (pinfunction "1_1") (pintype "passive"))
      (node (ref "L1") (pin "1") (pinfunction "1_1") (pintype "passive"))
      (node (ref "U2") (pin "45") (pinfunction "DVDD_45") (pintype "power_in"))
      (node (ref "U2") (pin "55") (pinfunction "DVDD_2_55") (pintype "power_in"))
    )
    (net (code "112") (name "Net-(U2-LOOP_FILTER)") (class "Default")
      (node (ref "R19") (pin "2") (pinfunction "2_2") (pintype "passive"))
      (node (ref "U2") (pin "27") (pinfunction "LOOP_FILTER_27") (pintype "input"))
    )
    (net (code "113") (name "Net-(U4-IN+)") (class "Default")
      (node (ref "R22") (pin "2") (pinfunction "2_2") (pintype "passive"))
      (node (ref "R23") (pin "2") (pinfunction "2_2") (pintype "passive"))
      (node (ref "U4") (pin "3") (pinfunction "IN+_3") (pintype "input"))
    )
    (net (code "114") (name "Net-(U4-IN-)") (class "Default")
      (node (ref "R24") (pin "1") (pinfunction "1_1") (pintype "passive"))
      (node (ref "R26") (pin "2") (pinfunction "2_2") (pintype "passive"))
      (node (ref "U4") (pin "4") (pinfunction "IN-_4") (pintype "input"))
    )
    (net (code "115") (name "Net-(U4-OUT)") (class "Default")
      (node (ref "R21") (pin "1") (pinfunction "1_1") (pintype "passive"))
      (node (ref "R24") (pin "2") (pinfunction "2_2") (pintype "passive"))
      (node (ref "U4") (pin "1") (pinfunction "OUT_1") (pintype "output"))
    )
    (net (code "116") (name "Net-(U4-VDD)") (class "Default")
      (node (ref "C33") (pin "1") (pinfunction "1_1") (pintype "passive"))
      (node (ref "C34") (pin "1") (pinfunction "1_1") (pintype "passive"))
      (node (ref "R20") (pin "1") (pinfunction "1_1") (pintype "passive"))
      (node (ref "U4") (pin "5") (pinfunction "VDD_5") (pintype "power_in"))
    )
    (net (code "117") (name "Net-(U5-CLPF)") (class "Default")
      (node (ref "C40") (pin "1") (pinfunction "1_1") (pintype "passive"))
      (node (ref "U5") (pin "9") (pinfunction "CLPF_9") (pintype "passive"))
    )
    (net (code "118") (name "Net-(U5-DECL)") (class "Default")
      (node (ref "C42") (pin "1") (pinfunction "1_1") (pintype "passive"))
      (node (ref "U5") (pin "6") (pinfunction "DECL_6") (pintype "input"))
    )
    (net (code "119") (name "Net-(U5-DECL_2)") (class "Default")
      (node (ref "C41") (pin "1") (pinfunction "1_1") (pintype "passive"))
      (node (ref "U5") (pin "3") (pinfunction "DECL_2_3") (pintype "input"))
    )
    (net (code "120") (name "Net-(U5-INHI)") (class "Default")
      (node (ref "C38") (pin "2") (pinfunction "2_2") (pintype "passive"))
      (node (ref "U5") (pin "4") (pinfunction "INHI_4") (pintype "input"))
    )
    (net (code "121") (name "Net-(U5-INLO)") (class "Default")
      (node (ref "C39") (pin "2") (pinfunction "2_2") (pintype "passive"))
      (node (ref "U5") (pin "5") (pinfunction "INLO_5") (pintype "input"))
    )
    (net (code "122") (name "Net-(U5-VREF)") (class "Default")
      (node (ref "U5") (pin "14") (pinfunction "VTGT_14") (pintype "power_in"))
      (node (ref "U5") (pin "15") (pinfunction "VREF_15") (pintype "output"))
    )
    (net (code "123") (name "Net-(U6-IN-)") (class "Default")
      (node (ref "C43") (pin "1") (pinfunction "1_1") (pintype "passive"))
      (node (ref "R26") (pin "1") (pinfunction "1_1") (pintype "passive"))
      (node (ref "U6") (pin "1") (pinfunction "OUT_1") (pintype "output"))
      (node (ref "U6") (pin "4") (pinfunction "IN-_4") (pintype "input"))
    )
    (net (code "124") (name "Net-(U6-VDD)") (class "Default")
      (node (ref "C44") (pin "1") (pinfunction "1_1") (pintype "passive"))
      (node (ref "C45") (pin "1") (pinfunction "1_1") (pintype "passive"))
      (node (ref "R25") (pin "1") (pinfunction "1_1") (pintype "passive"))
      (node (ref "U6") (pin "5") (pinfunction "VDD_5") (pintype "power_in"))
    )
    (net (code "125") (name "Net-(U7-IN+)") (class "Default")
      (node (ref "R30") (pin "2") (pinfunction "2_2") (pintype "passive"))
      (node (ref "U7") (pin "3") (pinfunction "IN+_3") (pintype "input"))
    )
    (net (code "126") (name "Net-(U7-IN-)") (class "Default")
      (node (ref "R29") (pin "1") (pinfunction "1_1") (pintype "passive"))
      (node (ref "U7") (pin "1") (pinfunction "OUT_1") (pintype "output"))
      (node (ref "U7") (pin "4") (pinfunction "IN-_4") (pintype "input"))
    )
    (net (code "127") (name "Net-(U7-VDD)") (class "Default")
      (node (ref "C46") (pin "1") (pinfunction "1_1") (pintype "passive"))
      (node (ref "C47") (pin "1") (pinfunction "1_1") (pintype "passive"))
      (node (ref "R27") (pin "1") (pinfunction "1_1") (pintype "passive"))
      (node (ref "U7") (pin "5") (pinfunction "VDD_5") (pintype "power_in"))
    )
    (net (code "128") (name "Net-(U8-INPA)") (class "Default")
      (node (ref "C53") (pin "2") (pinfunction "2_2") (pintype "passive"))
      (node (ref "U8") (pin "2") (pinfunction "INPA_2") (pintype "input"))
    )
    (net (code "129") (name "Net-(U8-INPB)") (class "Default")
      (node (ref "C56") (pin "2") (pinfunction "2_2") (pintype "passive"))
      (node (ref "U8") (pin "6") (pinfunction "INPB_6") (pintype "input"))
    )
    (net (code "130") (name "Net-(U8-MFLT)") (class "Default")
      (node (ref "C57") (pin "1") (pinfunction "1_1") (pintype "passive"))
      (node (ref "U8") (pin "14") (pinfunction "MFLT_14") (pintype "input"))
    )
    (net (code "131") (name "Net-(U8-MSET)") (class "Default")
      (node (ref "R31") (pin "2") (pinfunction "2_2") (pintype "passive"))
      (node (ref "R32") (pin "1") (pinfunction "1_1") (pintype "passive"))
      (node (ref "U8") (pin "12") (pinfunction "MSET_12") (pintype "input"))
    )
    (net (code "132") (name "Net-(U8-OFSA)") (class "Default")
      (node (ref "C50") (pin "2") (pinfunction "2_2") (pintype "passive"))
      (node (ref "U8") (pin "3") (pinfunction "OFSA_3") (pintype "input"))
    )
    (net (code "133") (name "Net-(U8-OFSB)") (class "Default")
      (node (ref "C51") (pin "2") (pinfunction "2_2") (pintype "passive"))
      (node (ref "U8") (pin "5") (pinfunction "OFSB_5") (pintype "input"))
    )
    (net (code "134") (name "Net-(U8-PFLT)") (class "Default")
      (node (ref "C52") (pin "1") (pinfunction "1_1") (pintype "passive"))
      (node (ref "U8") (pin "8") (pinfunction "PFLT_8") (pintype "output"))
    )
    (net (code "135") (name "Net-(U8-VPOS)") (class "Default")
      (node (ref "C49") (pin "2") (pinfunction "2_2") (pintype "passive"))
      (node (ref "R28") (pin "1") (pinfunction "1_1") (pintype "passive"))
      (node (ref "U8") (pin "4") (pinfunction "VPOS_4") (pintype "power_in"))
    )
    (net (code "136") (name "Net-(U8-VREF)") (class "Default")
      (node (ref "R32") (pin "2") (pinfunction "2_2") (pintype "passive"))
      (node (ref "U8") (pin "11") (pinfunction "VREF_11") (pintype "passive"))
    )
    (net (code "137") (name "Net-(U9-IN+)") (class "Default")
      (node (ref "R33") (pin "2") (pinfunction "2_2") (pintype "passive"))
      (node (ref "U9") (pin "3") (pinfunction "IN+_3") (pintype "input"))
    )
    (net (code "138") (name "Net-(U9-IN-)") (class "Default")
      (node (ref "R35") (pin "1") (pinfunction "1_1") (pintype "passive"))
      (node (ref "U9") (pin "1") (pinfunction "OUT_1") (pintype "output"))
      (node (ref "U9") (pin "4") (pinfunction "IN-_4") (pintype "input"))
    )
    (net (code "139") (name "Net-(U9-VDD)") (class "Default")
      (node (ref "C54") (pin "1") (pinfunction "1_1") (pintype "passive"))
      (node (ref "C55") (pin "1") (pinfunction "1_1") (pintype "passive"))
      (node (ref "R34") (pin "1") (pinfunction "1_1") (pintype "passive"))
      (node (ref "U9") (pin "5") (pinfunction "VDD_5") (pintype "power_in"))
    )
    (net (code "140") (name "Net-(U10-BST)") (class "Default")
      (node (ref "C117") (pin "2") (pinfunction "2_2") (pintype "passive"))
      (node (ref "U10") (pin "1") (pinfunction "BST_1") (pintype "power_in"))
    )
    (net (code "141") (name "Net-(U10-EN)") (class "Default")
      (node (ref "R51") (pin "1") (pinfunction "1_1") (pintype "passive"))
      (node (ref "R58") (pin "2") (pinfunction "2_2") (pintype "passive"))
      (node (ref "U10") (pin "4") (pinfunction "EN_4") (pintype "input"))
    )
    (net (code "142") (name "Net-(U10-FB)") (class "Default")
      (node (ref "R49") (pin "1") (pinfunction "1_1") (pintype "passive"))
      (node (ref "R50") (pin "2") (pinfunction "2_2") (pintype "passive"))
      (node (ref "U10") (pin "3") (pinfunction "FB_3") (pintype "input"))
    )
    (net (code "143") (name "Net-(U11-BST)") (class "Default")
      (node (ref "C113") (pin "2") (pinfunction "2_2") (pintype "passive"))
      (node (ref "U11") (pin "1") (pinfunction "BST_1") (pintype "power_in"))
    )
    (net (code "144") (name "Net-(U11-FB)") (class "Default")
      (node (ref "R53") (pin "1") (pinfunction "1_1") (pintype "passive"))
      (node (ref "R54") (pin "2") (pinfunction "2_2") (pintype "passive"))
      (node (ref "U11") (pin "3") (pinfunction "FB_3") (pintype "input"))
    )
    (net (code "145") (name "Net-(U12-BST)") (class "Default")
      (node (ref "C119") (pin "2") (pinfunction "2_2") (pintype "passive"))
      (node (ref "U12") (pin "1") (pinfunction "BST_1") (pintype "power_in"))
    )
    (net (code "146") (name "Net-(U12-FB)") (class "Default")
      (node (ref "R57") (pin "1") (pinfunction "1_1") (pintype "passive"))
      (node (ref "R59") (pin "2") (pinfunction "2_2") (pintype "passive"))
      (node (ref "U12") (pin "3") (pinfunction "FB_3") (pintype "input"))
    )
    (net (code "147") (name "PA7") (class "Default")
      (node (ref "U1") (pin "23") (pinfunction "PA7_23") (pintype "power_in"))
    )
    (net (code "148") (name "PC1") (class "Default")
      (node (ref "R8") (pin "2") (pinfunction "2_2") (pintype "passive"))
      (node (ref "U1") (pin "9") (pinfunction "PC1_9") (pintype "bidirectional"))
    )
    (net (code "149") (name "PC2") (class "Default")
      (node (ref "R10") (pin "2") (pinfunction "2_2") (pintype "passive"))
      (node (ref "U1") (pin "10") (pinfunction "PC2_10") (pintype "bidirectional"))
    )
    (net (code "150") (name "PHASE") (class "Default")
      (node (ref "R29") (pin "2") (pinfunction "2_2") (pintype "passive"))
      (node (ref "U1") (pin "27") (pinfunction "PB1_27") (pintype "bidirectional"))
    )
    (net (code "151") (name "PWR_DWN") (class "Default")
      (node (ref "R61") (pin "1") (pinfunction "1_1") (pintype "passive"))
      (node (ref "U2") (pin "4") (pinfunction "PWR_DWN_CTL_4") (pintype "input"))
    )
    (net (code "152") (name "RESET_DDS") (class "Default")
      (node (ref "U1") (pin "50") (pinfunction "PA15_50") (pintype "bidirectional"))
      (node (ref "U2") (pin "3") (pinfunction "MASTER_RESET_3") (pintype "input"))
    )
    (net (code "153") (name "RESET_FTDI") (class "Default")
      (node (ref "IC1") (pin "19") (pinfunction "~{RESET}_19") (pintype "input"))
      (node (ref "R2") (pin "1") (pinfunction "1_1") (pintype "passive"))
      (node (ref "R6") (pin "2") (pinfunction "2_2") (pintype "passive"))
      (node (ref "U1") (pin "40") (pinfunction "PC9_40") (pintype "bidirectional"))
    )
    (net (code "154") (name "RSRX") (class "Default")
      (node (ref "R3") (pin "2") (pinfunction "2_2") (pintype "passive"))
      (node (ref "U1") (pin "42") (pinfunction "PA9_42") (pintype "bidirectional"))
    )
    (net (code "155") (name "RST") (class "Default")
      (node (ref "ADM1") (pin "2") (pinfunction "E_2") (pintype "passive"))
      (node (ref "Q2") (pin "3") (pinfunction "C_3") (pintype "passive"))
      (node (ref "R4") (pin "1") (pinfunction "1_1") (pintype "passive"))
      (node (ref "S1") (pin "1") (pinfunction "P_1") (pintype "passive"))
      (node (ref "U1") (pin "7") (pinfunction "NRST_7") (pintype "output"))
    )
    (net (code "156") (name "RSTX") (class "Default")
      (node (ref "R1") (pin "2") (pinfunction "2_2") (pintype "passive"))
      (node (ref "U1") (pin "43") (pinfunction "PA10_43") (pintype "bidirectional"))
    )
    (net (code "157") (name "SCLK") (class "Default")
      (node (ref "U1") (pin "34") (pinfunction "PB13_34") (pintype "bidirectional"))
      (node (ref "U2") (pin "48") (pinfunction "SCLK_48") (pintype "input"))
    )
    (net (code "158") (name "SDIO") (class "Default")
      (node (ref "U1") (pin "36") (pinfunction "PB15_36") (pintype "bidirectional"))
      (node (ref "U2") (pin "50") (pinfunction "SDIO_0_50") (pintype "bidirectional"))
    )
    (net (code "159") (name "SDIO_1") (class "Default")
      (node (ref "U1") (pin "14") (pinfunction "PA0-WKUP_14") (pintype "bidirectional"))
      (node (ref "U2") (pin "51") (pinfunction "SDIO_1_51") (pintype "bidirectional"))
    )
    (net (code "160") (name "SDIO_2") (class "Default")
      (node (ref "U1") (pin "15") (pinfunction "PA1_15") (pintype "bidirectional"))
      (node (ref "U2") (pin "52") (pinfunction "SDIO_2_52") (pintype "bidirectional"))
    )
    (net (code "161") (name "SDIO_3") (class "Default")
      (node (ref "R64") (pin "2") (pinfunction "2_2") (pintype "passive"))
      (node (ref "U1") (pin "16") (pinfunction "PA2_16") (pintype "bidirectional"))
      (node (ref "U2") (pin "53") (pinfunction "SDIO_3_53") (pintype "bidirectional"))
    )
    (net (code "162") (name "S_DAC") (class "Default")
      (node (ref "U1") (pin "21") (pinfunction "PA5_21") (pintype "bidirectional"))
      (node (ref "U3") (pin "3") (pinfunction "IN+_3") (pintype "input"))
    )
    (net (code "163") (name "VCC") (class "Default")
      (node (ref "C116") (pin "2") (pinfunction "2_2") (pintype "passive"))
      (node (ref "C118") (pin "2") (pinfunction "2_2") (pintype "passive"))
      (node (ref "C26") (pin "1") (pinfunction "1_1") (pintype "passive"))
      (node (ref "C27") (pin "1") (pinfunction "1_1") (pintype "passive"))
      (node (ref "C30") (pin "1") (pinfunction "1_1") (pintype "passive"))
      (node (ref "C31") (pin "1") (pinfunction "1_1") (pintype "passive"))
      (node (ref "C32") (pin "1") (pinfunction "1_1") (pintype "passive"))
      (node (ref "L1") (pin "2") (pinfunction "2_2") (pintype "passive"))
      (node (ref "L2") (pin "2") (pinfunction "2_2") (pintype "passive"))
      (node (ref "L23COILCRAFT_LPS6225-103") (pin "P$2") (pinfunction "2_P$2") (pintype "passive"))
      (node (ref "R13") (pin "2") (pinfunction "2_2") (pintype "passive"))
      (node (ref "R14") (pin "2") (pinfunction "2_2") (pintype "passive"))
      (node (ref "R15") (pin "1") (pinfunction "1_1") (pintype "passive"))
      (node (ref "R17") (pin "2") (pinfunction "2_2") (pintype "passive"))
      (node (ref "R18") (pin "2") (pinfunction "2_2") (pintype "passive"))
      (node (ref "R57") (pin "2") (pinfunction "2_2") (pintype "passive"))
      (node (ref "TR1") (pin "P2") (pinfunction "S2_P2") (pintype "bidirectional"))
      (node (ref "TR2") (pin "P2") (pinfunction "S2_P2") (pintype "bidirectional"))
    )
    (net (code "164") (name "V_COR_OFFSET") (class "Default")
      (node (ref "U1") (pin "20") (pinfunction "PA4_20") (pintype "bidirectional"))
      (node (ref "U6") (pin "3") (pinfunction "IN+_3") (pintype "input"))
    )
    (net (code "165") (name "V_IN") (class "Default")
      (node (ref "C108") (pin "2") (pinfunction "2_2") (pintype "passive"))
      (node (ref "C109") (pin "2") (pinfunction "2_2") (pintype "passive"))
      (node (ref "C115") (pin "2") (pinfunction "2_2") (pintype "passive"))
      (node (ref "C120") (pin "+") (pinfunction "+_+") (pintype "passive"))
      (node (ref "R51") (pin "2") (pinfunction "2_2") (pintype "passive"))
      (node (ref "R52") (pin "2") (pinfunction "2_2") (pintype "passive"))
      (node (ref "R55") (pin "1") (pinfunction "1_1") (pintype "passive"))
      (node (ref "R56") (pin "2") (pinfunction "2_2") (pintype "passive"))
      (node (ref "R60") (pin "1") (pinfunction "1_1") (pintype "passive"))
      (node (ref "U10") (pin "5") (pinfunction "VIN_5") (pintype "input"))
      (node (ref "U11") (pin "5") (pinfunction "VIN_5") (pintype "input"))
      (node (ref "U12") (pin "5") (pinfunction "VIN_5") (pintype "input"))
      (node (ref "X3") (pin "1") (pinfunction "1_1") (pintype "passive"))
    )
    (net (code "166") (name "unconnected-(IC1-CBUS0-Pad23)") (class "Default")
      (node (ref "IC1") (pin "23") (pinfunction "CBUS0_23") (pintype "bidirectional"))
    )
    (net (code "167") (name "unconnected-(IC1-CBUS3-Pad14)") (class "Default")
      (node (ref "IC1") (pin "14") (pinfunction "CBUS3_14") (pintype "bidirectional"))
    )
    (net (code "168") (name "unconnected-(IC1-CBUS4-Pad12)") (class "Default")
      (node (ref "IC1") (pin "12") (pinfunction "CBUS4_12") (pintype "bidirectional"))
    )
    (net (code "169") (name "unconnected-(IC1-OSCI-Pad27)") (class "Default")
      (node (ref "IC1") (pin "27") (pinfunction "OSCI_27") (pintype "input"))
    )
    (net (code "170") (name "unconnected-(IC1-OSCO-Pad28)") (class "Default")
      (node (ref "IC1") (pin "28") (pinfunction "OSCO_28") (pintype "output"))
    )
    (net (code "171") (name "unconnected-(IC1-~{CTS}-Pad11)") (class "Default")
      (node (ref "IC1") (pin "11") (pinfunction "~{CTS}_11") (pintype "input"))
    )
    (net (code "172") (name "unconnected-(IC1-~{DCD}-Pad10)") (class "Default")
      (node (ref "IC1") (pin "10") (pinfunction "~{DCD}_10") (pintype "input"))
    )
    (net (code "173") (name "unconnected-(IC1-~{DSR}-Pad9)") (class "Default")
      (node (ref "IC1") (pin "9") (pinfunction "~{DSR}_9") (pintype "input"))
    )
    (net (code "174") (name "unconnected-(IC1-~{DTR}-Pad2)") (class "Default")
      (node (ref "IC1") (pin "2") (pinfunction "~{DTR}_2") (pintype "output"))
    )
    (net (code "175") (name "unconnected-(IC1-~{RI}-Pad6)") (class "Default")
      (node (ref "IC1") (pin "6") (pinfunction "~{RI}_6") (pintype "input"))
    )
    (net (code "176") (name "unconnected-(IC1-~{RTS}-Pad3)") (class "Default")
      (node (ref "IC1") (pin "3") (pinfunction "~{RTS}_3") (pintype "output"))
    )
    (net (code "177") (name "unconnected-(IC11-NC-Pad4)") (class "Default")
      (node (ref "IC11") (pin "4") (pinfunction "NC_4") (pintype "no_connect"))
    )
    (net (code "178") (name "unconnected-(U1-PA3-Pad17)") (class "Default")
      (node (ref "U1") (pin "17") (pinfunction "PA3_17") (pintype "bidirectional"))
    )
    (net (code "179") (name "unconnected-(U1-PA6-Pad22)") (class "Default")
      (node (ref "U1") (pin "22") (pinfunction "PA6_22") (pintype "bidirectional"))
    )
    (net (code "180") (name "unconnected-(U1-PA8-Pad41)") (class "Default")
      (node (ref "U1") (pin "41") (pinfunction "PA8_41") (pintype "bidirectional"))
    )
    (net (code "181") (name "unconnected-(U1-PB3-Pad55)") (class "Default")
      (node (ref "U1") (pin "55") (pinfunction "PB3_55") (pintype "bidirectional"))
    )
    (net (code "182") (name "unconnected-(U1-PB4-Pad56)") (class "Default")
      (node (ref "U1") (pin "56") (pinfunction "PB4_56") (pintype "bidirectional"))
    )
    (net (code "183") (name "unconnected-(U1-PB5-Pad57)") (class "Default")
      (node (ref "U1") (pin "57") (pinfunction "PB5_57") (pintype "bidirectional"))
    )
    (net (code "184") (name "unconnected-(U1-PB12-Pad33)") (class "Default")
      (node (ref "U1") (pin "33") (pinfunction "PB12_33") (pintype "bidirectional"))
    )
    (net (code "185") (name "unconnected-(U1-PB14-Pad35)") (class "Default")
      (node (ref "U1") (pin "35") (pinfunction "PB14_35") (pintype "bidirectional"))
    )
    (net (code "186") (name "unconnected-(U1-PC0-Pad8)") (class "Default")
      (node (ref "U1") (pin "8") (pinfunction "PC0_8") (pintype "bidirectional"))
    )
    (net (code "187") (name "unconnected-(U1-PC3-Pad11)") (class "Default")
      (node (ref "U1") (pin "11") (pinfunction "PC3_11") (pintype "bidirectional"))
    )
    (net (code "188") (name "unconnected-(U1-PC4-Pad24)") (class "Default")
      (node (ref "U1") (pin "24") (pinfunction "PC4_24") (pintype "passive"))
    )
    (net (code "189") (name "unconnected-(U1-PC5-Pad25)") (class "Default")
      (node (ref "U1") (pin "25") (pinfunction "PC5_25") (pintype "bidirectional"))
    )
    (net (code "190") (name "unconnected-(U1-PC6-Pad37)") (class "Default")
      (node (ref "U1") (pin "37") (pinfunction "PC6_37") (pintype "bidirectional"))
    )
    (net (code "191") (name "unconnected-(U1-PC7-Pad38)") (class "Default")
      (node (ref "U1") (pin "38") (pinfunction "PC7_38") (pintype "bidirectional"))
    )
    (net (code "192") (name "unconnected-(U1-PC8-Pad39)") (class "Default")
      (node (ref "U1") (pin "39") (pinfunction "PC8_39") (pintype "bidirectional"))
    )
    (net (code "193") (name "unconnected-(U1-PC10-Pad51)") (class "Default")
      (node (ref "U1") (pin "51") (pinfunction "PC10_51") (pintype "bidirectional"))
    )
    (net (code "194") (name "unconnected-(U1-PC11-Pad52)") (class "Default")
      (node (ref "U1") (pin "52") (pinfunction "PC11_52") (pintype "bidirectional"))
    )
    (net (code "195") (name "unconnected-(U1-PC12-Pad53)") (class "Default")
      (node (ref "U1") (pin "53") (pinfunction "PC12_53") (pintype "bidirectional"))
    )
    (net (code "196") (name "unconnected-(U1-PC15-OSC32_OUT-Pad4)") (class "Default")
      (node (ref "U1") (pin "4") (pinfunction "PC15-OSC32_OUT_4") (pintype "output"))
    )
    (net (code "197") (name "unconnected-(U1-PD2-Pad54)") (class "Default")
      (node (ref "U1") (pin "54") (pinfunction "PD2_54") (pintype "bidirectional"))
    )
    (net (code "198") (name "unconnected-(U1-VBAT-Pad1)") (class "Default")
      (node (ref "U1") (pin "1") (pinfunction "VBAT_1") (pintype "input"))
    )
    (net (code "199") (name "unconnected-(U2-NC-Pad32)") (class "Default")
      (node (ref "U2") (pin "32") (pinfunction "NC_32") (pintype "no_connect"))
    )
    (net (code "200") (name "unconnected-(U2-NC_2-Pad34)") (class "Default")
      (node (ref "U2") (pin "34") (pinfunction "NC_2_34") (pintype "no_connect"))
    )
    (net (code "201") (name "unconnected-(U2-NC_3-Pad38)") (class "Default")
      (node (ref "U2") (pin "38") (pinfunction "NC_3_38") (pintype "no_connect"))
    )
    (net (code "202") (name "unconnected-(U2-NC_4-Pad28)") (class "Default")
      (node (ref "U2") (pin "28") (pinfunction "NC_4_28") (pintype "no_connect"))
    )
    (net (code "203") (name "unconnected-(U2-P0-Pad40)") (class "Default")
      (node (ref "U2") (pin "40") (pinfunction "P0_40") (pintype "bidirectional"))
    )
    (net (code "204") (name "unconnected-(U2-P1-Pad41)") (class "Default")
      (node (ref "U2") (pin "41") (pinfunction "P1_41") (pintype "bidirectional"))
    )
    (net (code "205") (name "unconnected-(U2-P2-Pad42)") (class "Default")
      (node (ref "U2") (pin "42") (pinfunction "P2_42") (pintype "bidirectional"))
    )
    (net (code "206") (name "unconnected-(U2-P3-Pad43)") (class "Default")
      (node (ref "U2") (pin "43") (pinfunction "P3_43") (pintype "bidirectional"))
    )
    (net (code "207") (name "unconnected-(U2-SYNC_CLK-Pad54)") (class "Default")
      (node (ref "U2") (pin "54") (pinfunction "SYNC_CLK_54") (pintype "input"))
    )
    (net (code "208") (name "unconnected-(U2-SYNC_IN-Pad1)") (class "Default")
      (node (ref "U2") (pin "1") (pinfunction "SYNC_IN_1") (pintype "input"))
    )
    (net (code "209") (name "unconnected-(U2-SYNC_OUT-Pad2)") (class "Default")
      (node (ref "U2") (pin "2") (pinfunction "SYNC_OUT_2") (pintype "output"))
    )
    (net (code "210") (name "unconnected-(U5-CHPF-Pad2)") (class "Default")
      (node (ref "U5") (pin "2") (pinfunction "CHPF_2") (pintype "input"))
    )
    (net (code "211") (name "unconnected-(X1-Pad4)") (class "Default")
      (node (ref "X1") (pin "4") (pinfunction "4_4") (pintype "input"))
    )
    (net (code "212") (name "unconnected-(X2-Pad4)") (class "Default")
      (node (ref "X2") (pin "4") (pinfunction "4_4") (pintype "input"))
    )
  )
)
